# DragonBoard.net
KiCad netlist of a schematic drawn in EAGLE
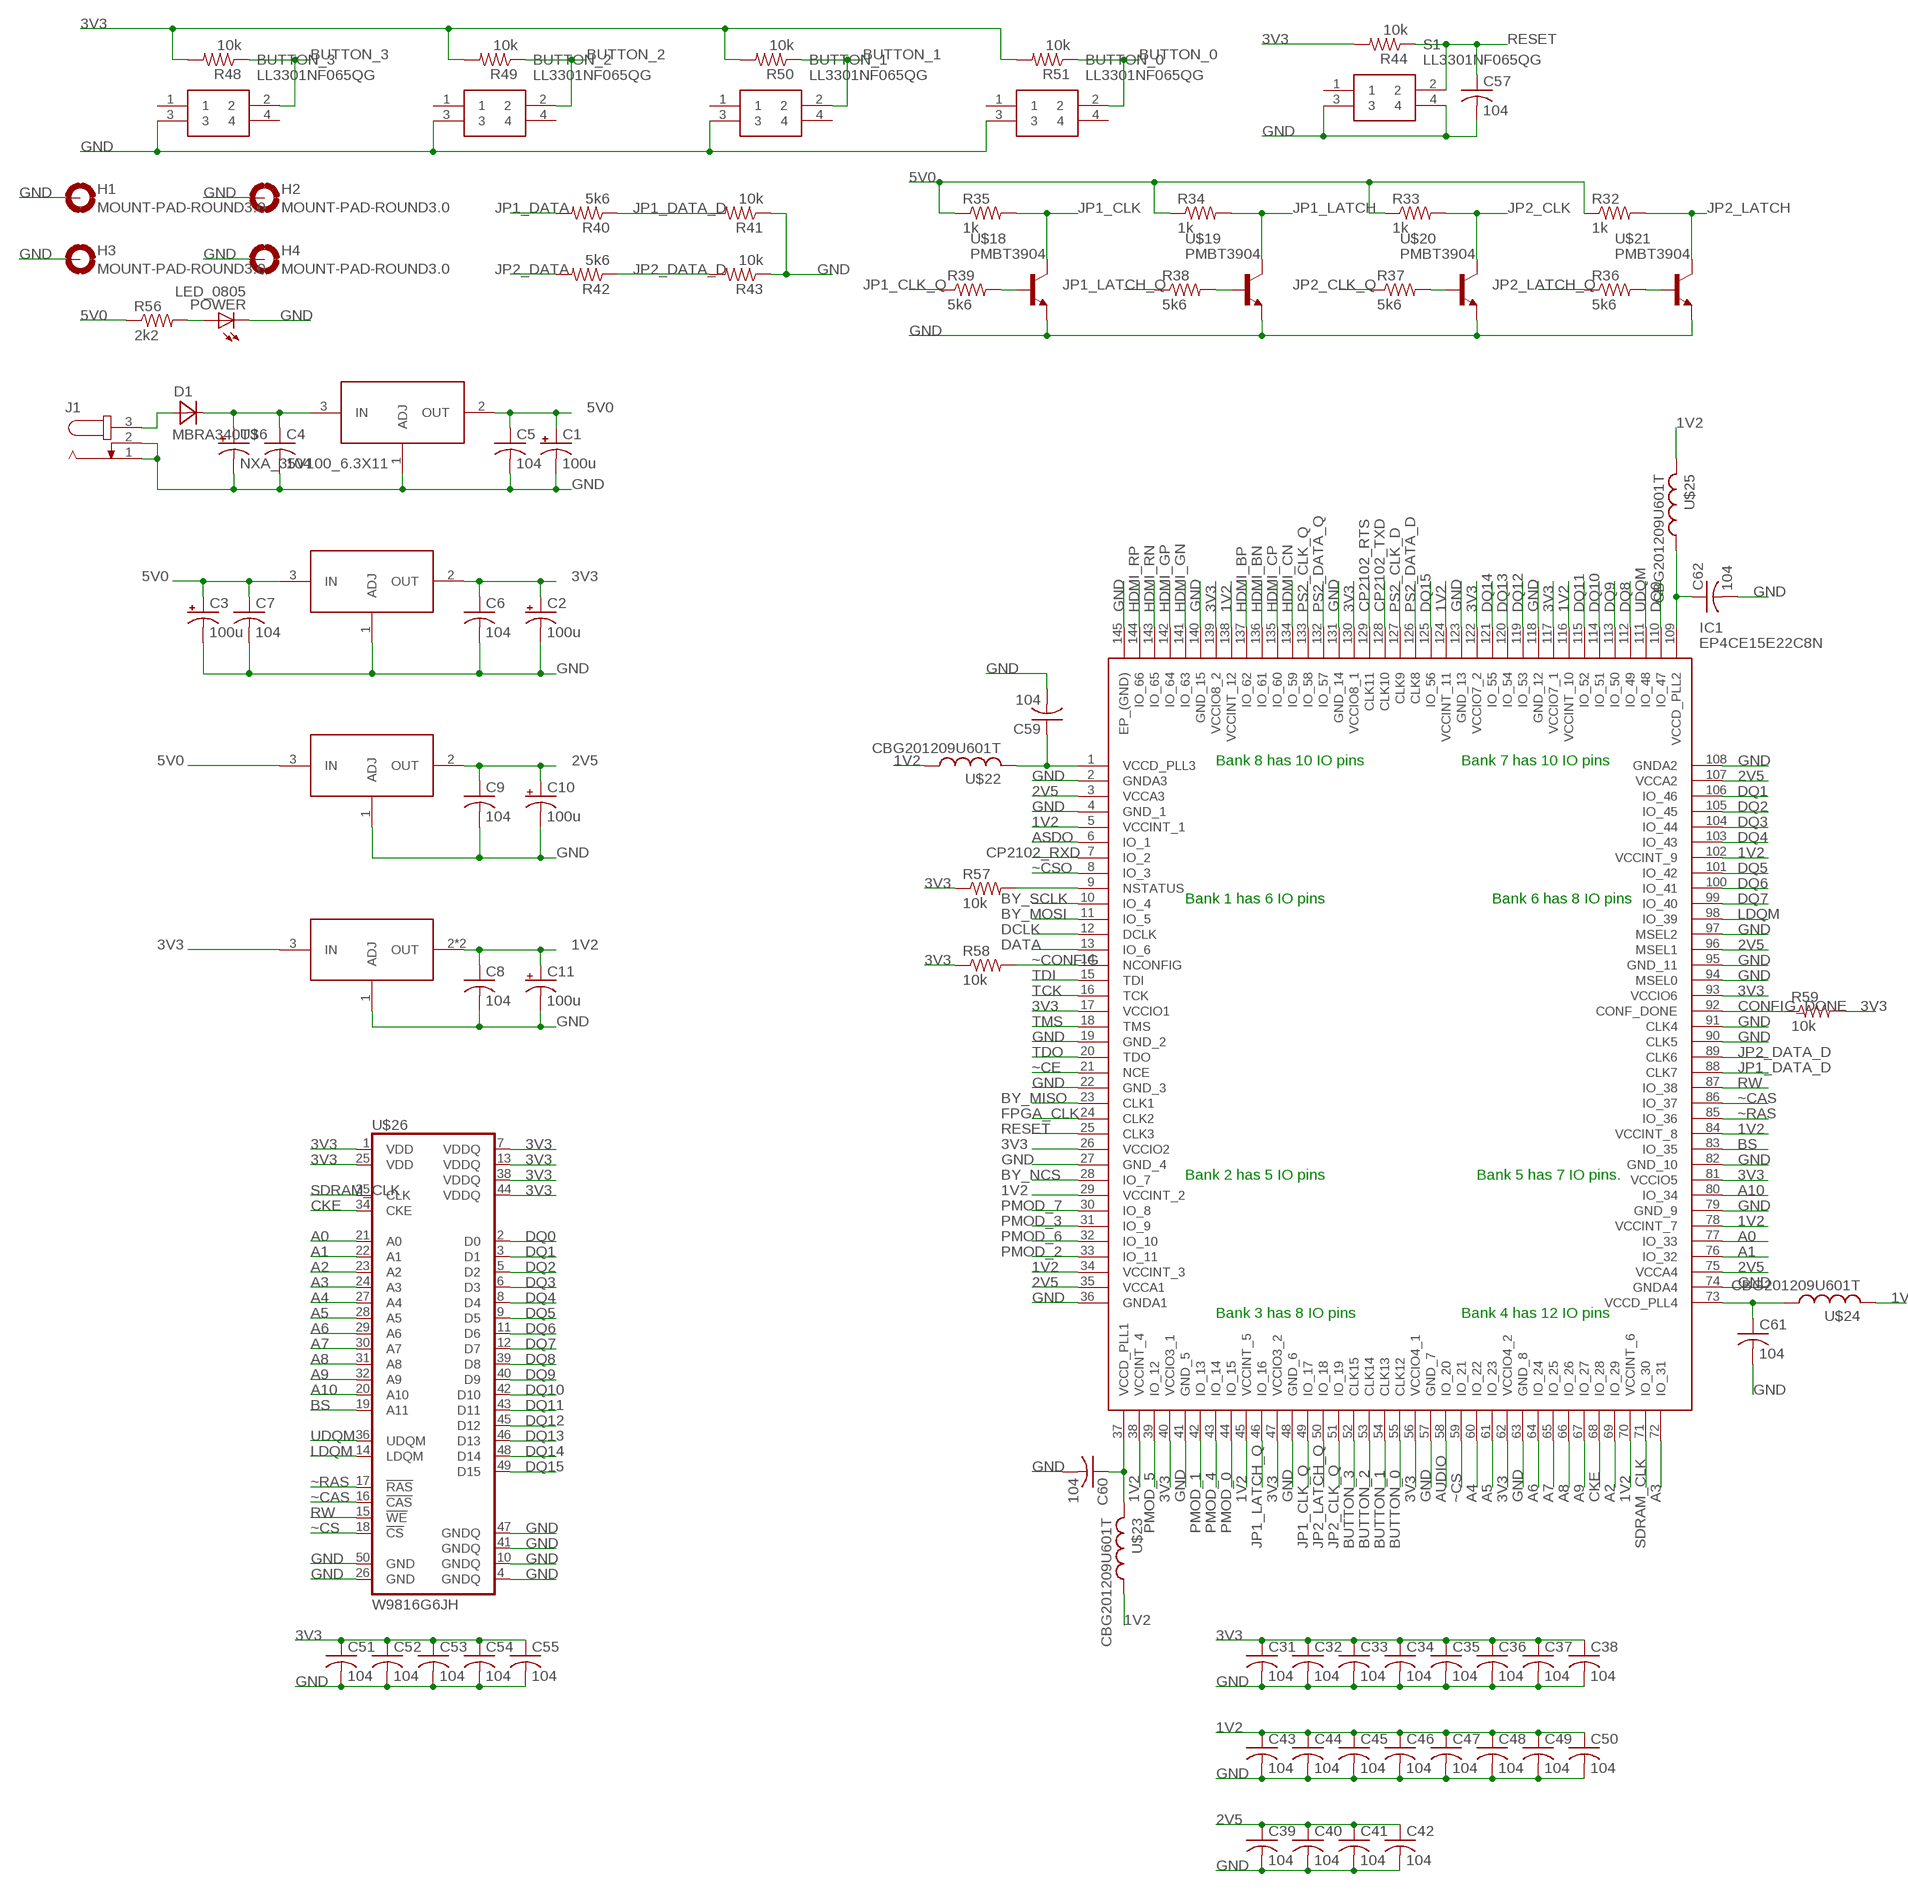
[diagram p0: schematic, sheet 1, part 1 of 2]
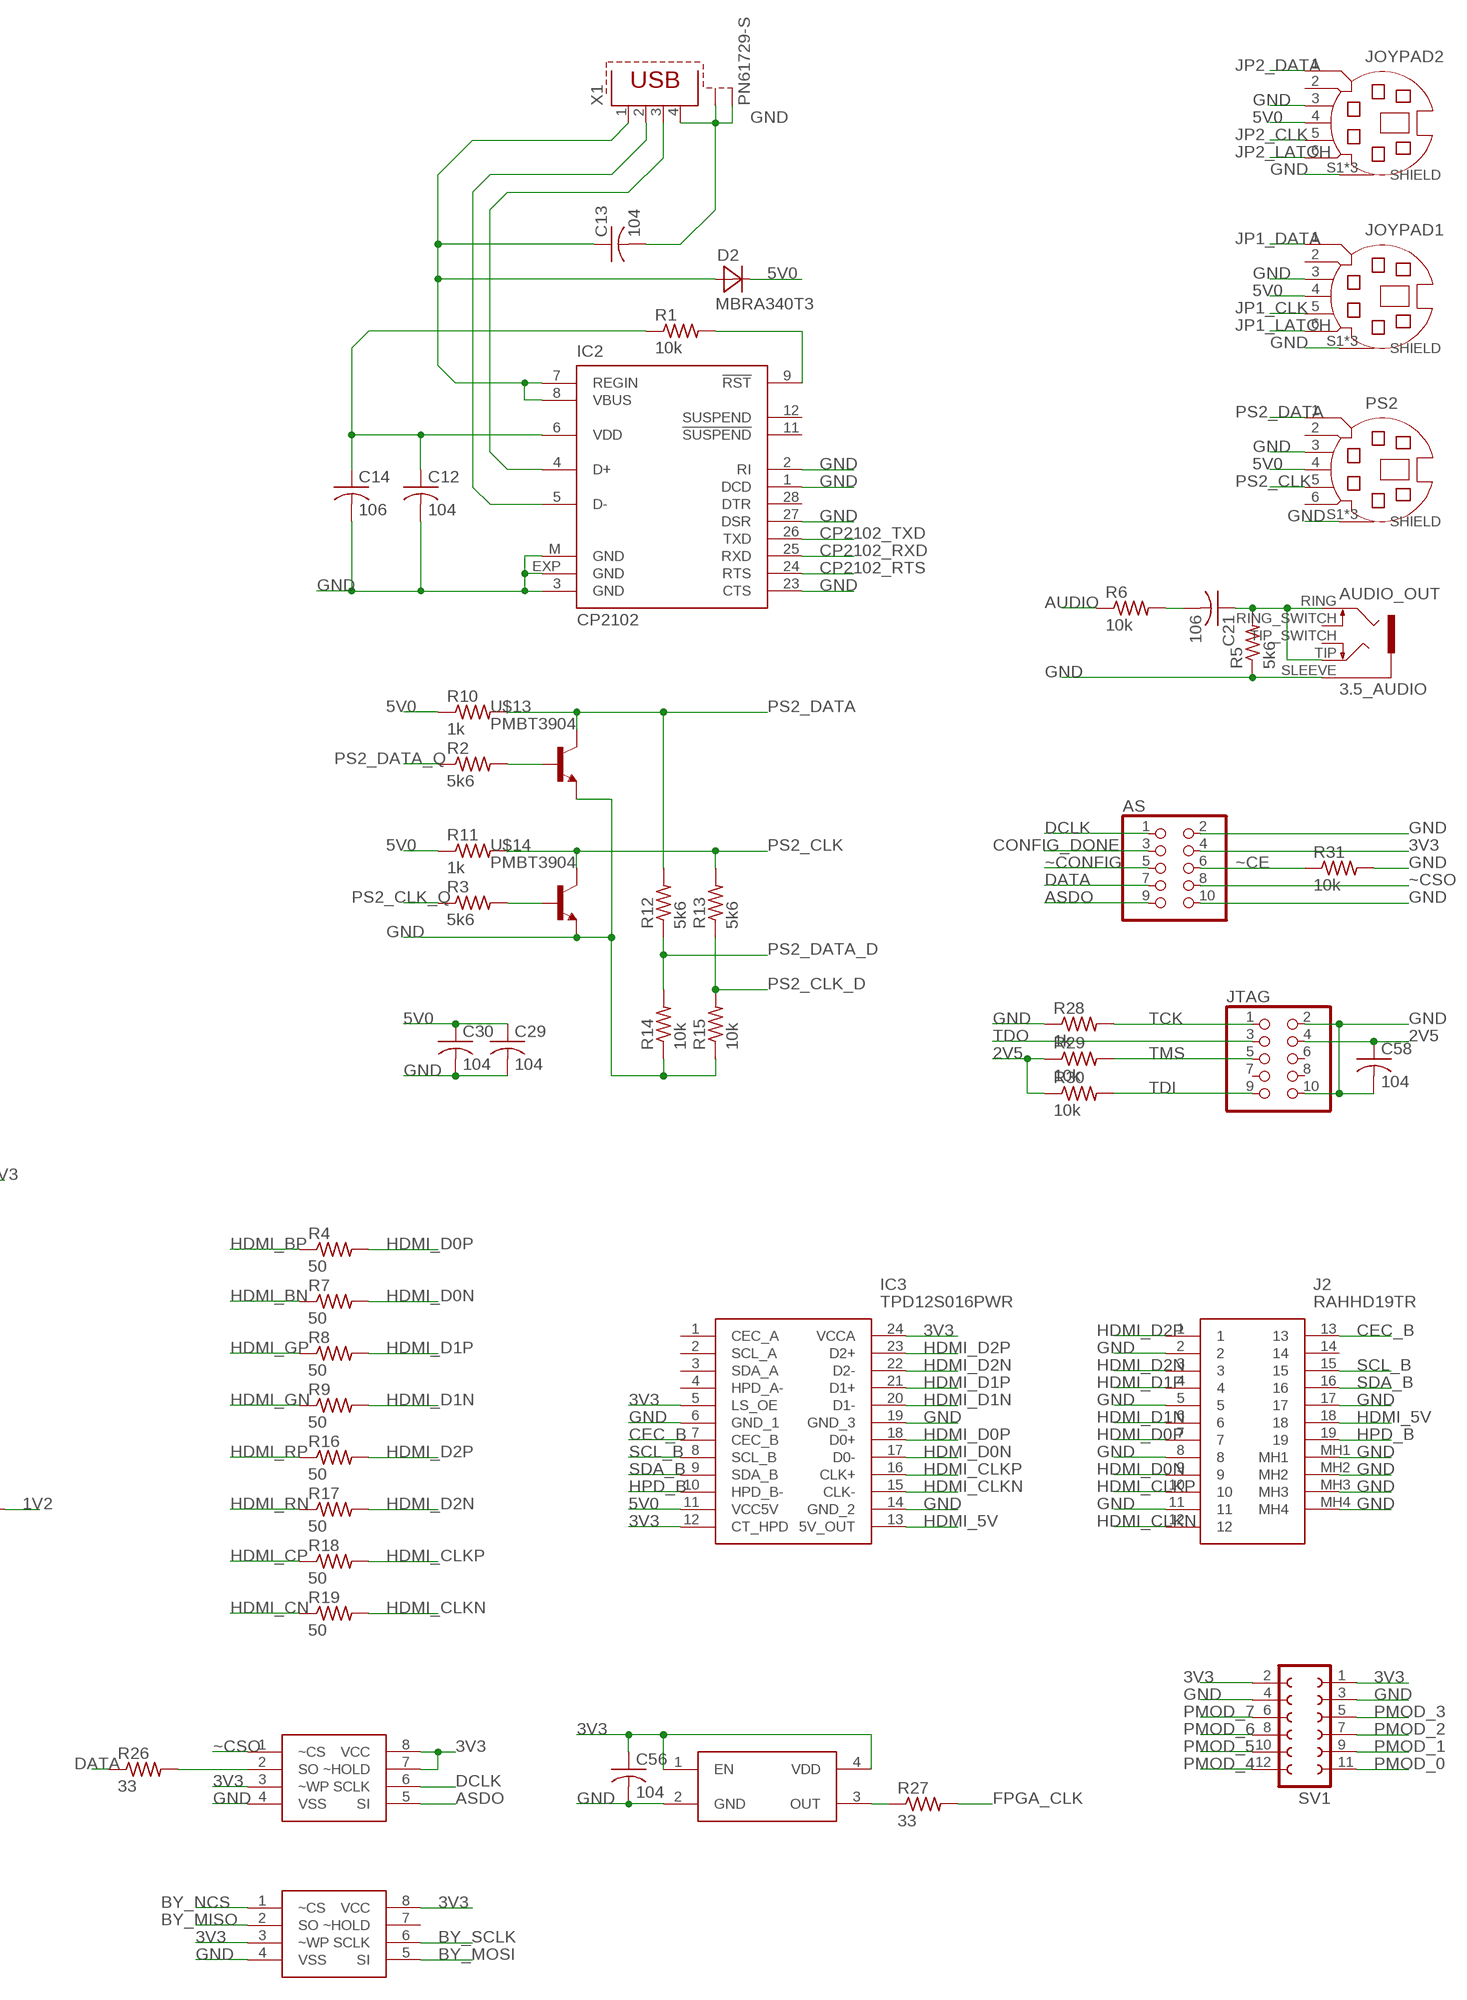
[diagram p1: schematic, sheet 1, part 2 of 2]

(export (version "E")
  (design (tool "Eeschema 10.0.6"))
  (components
    (comp (ref "AS")
      (value "PINHD-2X5")
      (footprint "eagle-import:2X05")
      (libsource (lib "eagle-import") (part "PINHD-2X5"))
    )
    (comp (ref "AUDIO_OUT")
      (value "3.5_AUDIO")
      (footprint "eagle-import:3.5_AUDIO")
      (libsource (lib "eagle-import") (part "3.5_AUDIO"))
    )
    (comp (ref "BUTTON_0")
      (value "LL3301NF065QG")
      (footprint "eagle-import:LL3301NF065QG")
      (fields (field (name "MOUSER_PART_NUMBER") "612-LL3301NF065QG"))
      (libsource (lib "eagle-import") (part "LL3301NF065QG"))
    )
    (comp (ref "BUTTON_1")
      (value "LL3301NF065QG")
      (footprint "eagle-import:LL3301NF065QG")
      (fields (field (name "MOUSER_PART_NUMBER") "612-LL3301NF065QG"))
      (libsource (lib "eagle-import") (part "LL3301NF065QG"))
    )
    (comp (ref "BUTTON_2")
      (value "LL3301NF065QG")
      (footprint "eagle-import:LL3301NF065QG")
      (fields (field (name "MOUSER_PART_NUMBER") "612-LL3301NF065QG"))
      (libsource (lib "eagle-import") (part "LL3301NF065QG"))
    )
    (comp (ref "BUTTON_3")
      (value "LL3301NF065QG")
      (footprint "eagle-import:LL3301NF065QG")
      (fields (field (name "MOUSER_PART_NUMBER") "612-LL3301NF065QG"))
      (libsource (lib "eagle-import") (part "LL3301NF065QG"))
    )
    (comp (ref "C1")
      (value "100u")
      (footprint "eagle-import:UD-6,3X5,8_NICHICON")
      (libsource (lib "eagle-import") (part "CPOL-USUD-6,3X5,8"))
    )
    (comp (ref "C2")
      (value "100u")
      (footprint "eagle-import:UD-6,3X5,8_NICHICON")
      (libsource (lib "eagle-import") (part "CPOL-USUD-6,3X5,8"))
    )
    (comp (ref "C3")
      (value "100u")
      (footprint "eagle-import:UD-6,3X5,8_NICHICON")
      (libsource (lib "eagle-import") (part "CPOL-USUD-6,3X5,8"))
    )
    (comp (ref "C4")
      (value "104")
      (footprint "eagle-import:C0805")
      (libsource (lib "eagle-import") (part "C-USC0805"))
    )
    (comp (ref "C5")
      (value "104")
      (footprint "eagle-import:C0805")
      (libsource (lib "eagle-import") (part "C-USC0805"))
    )
    (comp (ref "C6")
      (value "104")
      (footprint "eagle-import:C0805")
      (libsource (lib "eagle-import") (part "C-USC0805"))
    )
    (comp (ref "C7")
      (value "104")
      (footprint "eagle-import:C0805")
      (libsource (lib "eagle-import") (part "C-USC0805"))
    )
    (comp (ref "C8")
      (value "104")
      (footprint "eagle-import:C0805")
      (libsource (lib "eagle-import") (part "C-USC0805"))
    )
    (comp (ref "C9")
      (value "104")
      (footprint "eagle-import:C0805")
      (libsource (lib "eagle-import") (part "C-USC0805"))
    )
    (comp (ref "C10")
      (value "100u")
      (footprint "eagle-import:UD-6,3X5,8_NICHICON")
      (libsource (lib "eagle-import") (part "CPOL-USUD-6,3X5,8"))
    )
    (comp (ref "C11")
      (value "100u")
      (footprint "eagle-import:UD-6,3X5,8_NICHICON")
      (libsource (lib "eagle-import") (part "CPOL-USUD-6,3X5,8"))
    )
    (comp (ref "C12")
      (value "104")
      (footprint "eagle-import:C0805")
      (libsource (lib "eagle-import") (part "C-USC0805"))
    )
    (comp (ref "C13")
      (value "104")
      (footprint "eagle-import:C0805")
      (libsource (lib "eagle-import") (part "C-USC0805"))
    )
    (comp (ref "C14")
      (value "106")
      (footprint "eagle-import:C1206")
      (libsource (lib "eagle-import") (part "C-USC1206"))
    )
    (comp (ref "C21")
      (value "106")
      (footprint "eagle-import:C1206")
      (libsource (lib "eagle-import") (part "C-USC1206"))
    )
    (comp (ref "C29")
      (value "104")
      (footprint "eagle-import:C0805")
      (libsource (lib "eagle-import") (part "C-USC0805"))
    )
    (comp (ref "C30")
      (value "104")
      (footprint "eagle-import:C0805")
      (libsource (lib "eagle-import") (part "C-USC0805"))
    )
    (comp (ref "C31")
      (value "104")
      (footprint "eagle-import:C0805")
      (libsource (lib "eagle-import") (part "C-USC0805"))
    )
    (comp (ref "C32")
      (value "104")
      (footprint "eagle-import:C0805")
      (libsource (lib "eagle-import") (part "C-USC0805"))
    )
    (comp (ref "C33")
      (value "104")
      (footprint "eagle-import:C0805")
      (libsource (lib "eagle-import") (part "C-USC0805"))
    )
    (comp (ref "C34")
      (value "104")
      (footprint "eagle-import:C0805")
      (libsource (lib "eagle-import") (part "C-USC0805"))
    )
    (comp (ref "C35")
      (value "104")
      (footprint "eagle-import:C0805")
      (libsource (lib "eagle-import") (part "C-USC0805"))
    )
    (comp (ref "C36")
      (value "104")
      (footprint "eagle-import:C0805")
      (libsource (lib "eagle-import") (part "C-USC0805"))
    )
    (comp (ref "C37")
      (value "104")
      (footprint "eagle-import:C0805")
      (libsource (lib "eagle-import") (part "C-USC0805"))
    )
    (comp (ref "C38")
      (value "104")
      (footprint "eagle-import:C0805")
      (libsource (lib "eagle-import") (part "C-USC0805"))
    )
    (comp (ref "C39")
      (value "104")
      (footprint "eagle-import:C0805")
      (libsource (lib "eagle-import") (part "C-USC0805"))
    )
    (comp (ref "C40")
      (value "104")
      (footprint "eagle-import:C0805")
      (libsource (lib "eagle-import") (part "C-USC0805"))
    )
    (comp (ref "C41")
      (value "104")
      (footprint "eagle-import:C0805")
      (libsource (lib "eagle-import") (part "C-USC0805"))
    )
    (comp (ref "C42")
      (value "104")
      (footprint "eagle-import:C0805")
      (libsource (lib "eagle-import") (part "C-USC0805"))
    )
    (comp (ref "C43")
      (value "104")
      (footprint "eagle-import:C0805")
      (libsource (lib "eagle-import") (part "C-USC0805"))
    )
    (comp (ref "C44")
      (value "104")
      (footprint "eagle-import:C0805")
      (libsource (lib "eagle-import") (part "C-USC0805"))
    )
    (comp (ref "C45")
      (value "104")
      (footprint "eagle-import:C0805")
      (libsource (lib "eagle-import") (part "C-USC0805"))
    )
    (comp (ref "C46")
      (value "104")
      (footprint "eagle-import:C0805")
      (libsource (lib "eagle-import") (part "C-USC0805"))
    )
    (comp (ref "C47")
      (value "104")
      (footprint "eagle-import:C0805")
      (libsource (lib "eagle-import") (part "C-USC0805"))
    )
    (comp (ref "C48")
      (value "104")
      (footprint "eagle-import:C0805")
      (libsource (lib "eagle-import") (part "C-USC0805"))
    )
    (comp (ref "C49")
      (value "104")
      (footprint "eagle-import:C0805")
      (libsource (lib "eagle-import") (part "C-USC0805"))
    )
    (comp (ref "C50")
      (value "104")
      (footprint "eagle-import:C0805")
      (libsource (lib "eagle-import") (part "C-USC0805"))
    )
    (comp (ref "C51")
      (value "104")
      (footprint "eagle-import:C0805")
      (libsource (lib "eagle-import") (part "C-USC0805"))
    )
    (comp (ref "C52")
      (value "104")
      (footprint "eagle-import:C0805")
      (libsource (lib "eagle-import") (part "C-USC0805"))
    )
    (comp (ref "C53")
      (value "104")
      (footprint "eagle-import:C0805")
      (libsource (lib "eagle-import") (part "C-USC0805"))
    )
    (comp (ref "C54")
      (value "104")
      (footprint "eagle-import:C0805")
      (libsource (lib "eagle-import") (part "C-USC0805"))
    )
    (comp (ref "C55")
      (value "104")
      (footprint "eagle-import:C0805")
      (libsource (lib "eagle-import") (part "C-USC0805"))
    )
    (comp (ref "C56")
      (value "104")
      (footprint "eagle-import:C0805")
      (libsource (lib "eagle-import") (part "C-USC0805"))
    )
    (comp (ref "C57")
      (value "104")
      (footprint "eagle-import:C0805")
      (libsource (lib "eagle-import") (part "C-USC0805"))
    )
    (comp (ref "C58")
      (value "104")
      (footprint "eagle-import:C0805")
      (libsource (lib "eagle-import") (part "C-USC0805"))
    )
    (comp (ref "C59")
      (value "104")
      (footprint "eagle-import:C0805")
      (libsource (lib "eagle-import") (part "C-USC0805"))
    )
    (comp (ref "C60")
      (value "104")
      (footprint "eagle-import:C0805")
      (libsource (lib "eagle-import") (part "C-USC0805"))
    )
    (comp (ref "C61")
      (value "104")
      (footprint "eagle-import:C0805")
      (libsource (lib "eagle-import") (part "C-USC0805"))
    )
    (comp (ref "C62")
      (value "104")
      (footprint "eagle-import:C0805")
      (libsource (lib "eagle-import") (part "C-USC0805"))
    )
    (comp (ref "D1")
      (value "MBRA340T3")
      (footprint "eagle-import:SMA")
      (libsource (lib "eagle-import") (part "MBRA340T3"))
    )
    (comp (ref "D2")
      (value "MBRA340T3")
      (footprint "eagle-import:SMA")
      (libsource (lib "eagle-import") (part "MBRA340T3"))
    )
    (comp (ref "H1")
      (value "MOUNT-PAD-ROUND3.0")
      (footprint "eagle-import:3,0-PAD")
      (libsource (lib "eagle-import") (part "MOUNT-PAD-ROUND3.0"))
    )
    (comp (ref "H2")
      (value "MOUNT-PAD-ROUND3.0")
      (footprint "eagle-import:3,0-PAD")
      (libsource (lib "eagle-import") (part "MOUNT-PAD-ROUND3.0"))
    )
    (comp (ref "H3")
      (value "MOUNT-PAD-ROUND3.0")
      (footprint "eagle-import:3,0-PAD")
      (libsource (lib "eagle-import") (part "MOUNT-PAD-ROUND3.0"))
    )
    (comp (ref "H4")
      (value "MOUNT-PAD-ROUND3.0")
      (footprint "eagle-import:3,0-PAD")
      (libsource (lib "eagle-import") (part "MOUNT-PAD-ROUND3.0"))
    )
    (comp (ref "IC1")
      (value "EP4CE15E22C8N")
      (footprint "eagle-import:QFP50P2200X2200X165-145N")
      (fields (field (name "MOUSER_PART_NUMBER") "989-EP4CE15E22C8N"))
      (libsource (lib "eagle-import") (part "EP4CE15E22C8N"))
    )
    (comp (ref "IC2")
      (value "CP2102")
      (footprint "eagle-import:MLP28")
      (fields (field (name "MF") "FARNELL") (field (name "MPN") "CP2102-GM"))
      (libsource (lib "eagle-import") (part "CP2102"))
    )
    (comp (ref "IC3")
      (value "TPD12S016PWR")
      (footprint "eagle-import:SOP65P640X120-24N")
      (fields (field (name "MOUSER_PART_NUMBER") "595-TPD12S016PWR"))
      (libsource (lib "eagle-import") (part "TPD12S016PWR"))
    )
    (comp (ref "J1")
      (value "JACK-PLUG1")
      (footprint "eagle-import:SPC4078")
      (libsource (lib "eagle-import") (part "JACK-PLUG1"))
    )
    (comp (ref "J2")
      (value "RAHHD19TR")
      (footprint "eagle-import:RAHHD19TR")
      (fields (field (name "MOUSER_PART_NUMBER") "502-RAHHD19TR"))
      (libsource (lib "eagle-import") (part "RAHHD19TR"))
    )
    (comp (ref "JOYPAD1")
      (value "MD06SS")
      (footprint "eagle-import:MDIN06SS")
      (libsource (lib "eagle-import") (part "MD06SS"))
    )
    (comp (ref "JOYPAD2")
      (value "MD06SS")
      (footprint "eagle-import:MDIN06SS")
      (libsource (lib "eagle-import") (part "MD06SS"))
    )
    (comp (ref "JTAG")
      (value "PINHD-2X5")
      (footprint "eagle-import:2X05")
      (libsource (lib "eagle-import") (part "PINHD-2X5"))
    )
    (comp (ref "POWER")
      (value "LED_0805")
      (footprint "eagle-import:CHIP-LED0805")
      (libsource (lib "eagle-import") (part "LED_0805"))
    )
    (comp (ref "PS2")
      (value "MD06SS")
      (footprint "eagle-import:MDIN06SS")
      (libsource (lib "eagle-import") (part "MD06SS"))
    )
    (comp (ref "R1")
      (value "10k")
      (footprint "eagle-import:R0805")
      (libsource (lib "eagle-import") (part "R-US_R0805"))
    )
    (comp (ref "R2")
      (value "5k6")
      (footprint "eagle-import:R0805")
      (libsource (lib "eagle-import") (part "R-US_R0805"))
    )
    (comp (ref "R3")
      (value "5k6")
      (footprint "eagle-import:R0805")
      (libsource (lib "eagle-import") (part "R-US_R0805"))
    )
    (comp (ref "R4")
      (value "50")
      (footprint "eagle-import:R0805")
      (libsource (lib "eagle-import") (part "R-US_R0805"))
    )
    (comp (ref "R5")
      (value "5k6")
      (footprint "eagle-import:R0805")
      (libsource (lib "eagle-import") (part "R-US_R0805"))
    )
    (comp (ref "R6")
      (value "10k")
      (footprint "eagle-import:R0805")
      (libsource (lib "eagle-import") (part "R-US_R0805"))
    )
    (comp (ref "R7")
      (value "50")
      (footprint "eagle-import:R0805")
      (libsource (lib "eagle-import") (part "R-US_R0805"))
    )
    (comp (ref "R8")
      (value "50")
      (footprint "eagle-import:R0805")
      (libsource (lib "eagle-import") (part "R-US_R0805"))
    )
    (comp (ref "R9")
      (value "50")
      (footprint "eagle-import:R0805")
      (libsource (lib "eagle-import") (part "R-US_R0805"))
    )
    (comp (ref "R10")
      (value "1k")
      (footprint "eagle-import:R0805")
      (libsource (lib "eagle-import") (part "R-US_R0805"))
    )
    (comp (ref "R11")
      (value "1k")
      (footprint "eagle-import:R0805")
      (libsource (lib "eagle-import") (part "R-US_R0805"))
    )
    (comp (ref "R12")
      (value "5k6")
      (footprint "eagle-import:R0805")
      (libsource (lib "eagle-import") (part "R-US_R0805"))
    )
    (comp (ref "R13")
      (value "5k6")
      (footprint "eagle-import:R0805")
      (libsource (lib "eagle-import") (part "R-US_R0805"))
    )
    (comp (ref "R14")
      (value "10k")
      (footprint "eagle-import:R0805")
      (libsource (lib "eagle-import") (part "R-US_R0805"))
    )
    (comp (ref "R15")
      (value "10k")
      (footprint "eagle-import:R0805")
      (libsource (lib "eagle-import") (part "R-US_R0805"))
    )
    (comp (ref "R16")
      (value "50")
      (footprint "eagle-import:R0805")
      (libsource (lib "eagle-import") (part "R-US_R0805"))
    )
    (comp (ref "R17")
      (value "50")
      (footprint "eagle-import:R0805")
      (libsource (lib "eagle-import") (part "R-US_R0805"))
    )
    (comp (ref "R18")
      (value "50")
      (footprint "eagle-import:R0805")
      (libsource (lib "eagle-import") (part "R-US_R0805"))
    )
    (comp (ref "R19")
      (value "50")
      (footprint "eagle-import:R0805")
      (libsource (lib "eagle-import") (part "R-US_R0805"))
    )
    (comp (ref "R26")
      (value "33")
      (footprint "eagle-import:R0805")
      (libsource (lib "eagle-import") (part "R-US_R0805"))
    )
    (comp (ref "R27")
      (value "33")
      (footprint "eagle-import:R0805")
      (libsource (lib "eagle-import") (part "R-US_R0805"))
    )
    (comp (ref "R28")
      (value "1k")
      (footprint "eagle-import:R0805")
      (libsource (lib "eagle-import") (part "R-US_R0805"))
    )
    (comp (ref "R29")
      (value "10k")
      (footprint "eagle-import:R0805")
      (libsource (lib "eagle-import") (part "R-US_R0805"))
    )
    (comp (ref "R30")
      (value "10k")
      (footprint "eagle-import:R0805")
      (libsource (lib "eagle-import") (part "R-US_R0805"))
    )
    (comp (ref "R31")
      (value "10k")
      (footprint "eagle-import:R0805")
      (libsource (lib "eagle-import") (part "R-US_R0805"))
    )
    (comp (ref "R32")
      (value "1k")
      (footprint "eagle-import:R0805")
      (libsource (lib "eagle-import") (part "R-US_R0805"))
    )
    (comp (ref "R33")
      (value "1k")
      (footprint "eagle-import:R0805")
      (libsource (lib "eagle-import") (part "R-US_R0805"))
    )
    (comp (ref "R34")
      (value "1k")
      (footprint "eagle-import:R0805")
      (libsource (lib "eagle-import") (part "R-US_R0805"))
    )
    (comp (ref "R35")
      (value "1k")
      (footprint "eagle-import:R0805")
      (libsource (lib "eagle-import") (part "R-US_R0805"))
    )
    (comp (ref "R36")
      (value "5k6")
      (footprint "eagle-import:R0805")
      (libsource (lib "eagle-import") (part "R-US_R0805"))
    )
    (comp (ref "R37")
      (value "5k6")
      (footprint "eagle-import:R0805")
      (libsource (lib "eagle-import") (part "R-US_R0805"))
    )
    (comp (ref "R38")
      (value "5k6")
      (footprint "eagle-import:R0805")
      (libsource (lib "eagle-import") (part "R-US_R0805"))
    )
    (comp (ref "R39")
      (value "5k6")
      (footprint "eagle-import:R0805")
      (libsource (lib "eagle-import") (part "R-US_R0805"))
    )
    (comp (ref "R40")
      (value "5k6")
      (footprint "eagle-import:R0805")
      (libsource (lib "eagle-import") (part "R-US_R0805"))
    )
    (comp (ref "R41")
      (value "10k")
      (footprint "eagle-import:R0805")
      (libsource (lib "eagle-import") (part "R-US_R0805"))
    )
    (comp (ref "R42")
      (value "5k6")
      (footprint "eagle-import:R0805")
      (libsource (lib "eagle-import") (part "R-US_R0805"))
    )
    (comp (ref "R43")
      (value "10k")
      (footprint "eagle-import:R0805")
      (libsource (lib "eagle-import") (part "R-US_R0805"))
    )
    (comp (ref "R44")
      (value "10k")
      (footprint "eagle-import:R0805")
      (libsource (lib "eagle-import") (part "R-US_R0805"))
    )
    (comp (ref "R48")
      (value "10k")
      (footprint "eagle-import:R0805")
      (libsource (lib "eagle-import") (part "R-US_R0805"))
    )
    (comp (ref "R49")
      (value "10k")
      (footprint "eagle-import:R0805")
      (libsource (lib "eagle-import") (part "R-US_R0805"))
    )
    (comp (ref "R50")
      (value "10k")
      (footprint "eagle-import:R0805")
      (libsource (lib "eagle-import") (part "R-US_R0805"))
    )
    (comp (ref "R51")
      (value "10k")
      (footprint "eagle-import:R0805")
      (libsource (lib "eagle-import") (part "R-US_R0805"))
    )
    (comp (ref "R56")
      (value "2k2")
      (footprint "eagle-import:R0805")
      (libsource (lib "eagle-import") (part "R-US_R0805"))
    )
    (comp (ref "R57")
      (value "10k")
      (footprint "eagle-import:R0805")
      (libsource (lib "eagle-import") (part "R-US_R0805"))
    )
    (comp (ref "R58")
      (value "10k")
      (footprint "eagle-import:R0805")
      (libsource (lib "eagle-import") (part "R-US_R0805"))
    )
    (comp (ref "R59")
      (value "10k")
      (footprint "eagle-import:R0805")
      (libsource (lib "eagle-import") (part "R-US_R0805"))
    )
    (comp (ref "S1")
      (value "LL3301NF065QG")
      (footprint "eagle-import:LL3301NF065QG")
      (fields (field (name "MOUSER_PART_NUMBER") "612-LL3301NF065QG"))
      (libsource (lib "eagle-import") (part "LL3301NF065QG"))
    )
    (comp (ref "SV1")
      (value "FE06-2W")
      (footprint "eagle-import:FE06-2W")
      (libsource (lib "eagle-import") (part "FE06-2W"))
    )
    (comp (ref "U$1")
      (value "BY25Q16BS")
      (footprint "eagle-import:SO08")
      (libsource (lib "eagle-import") (part "BY25Q16BS"))
    )
    (comp (ref "U$5")
      (value "LM1086")
      (footprint "eagle-import:D2PACK")
      (libsource (lib "eagle-import") (part "LM1086"))
    )
    (comp (ref "U$6")
      (value "NXA_35V100_6.3X11")
      (footprint "eagle-import:NXA_35V100_6.3X11")
      (libsource (lib "eagle-import") (part "NXA_35V100_6.3X11"))
    )
    (comp (ref "U$7")
      (value "LD1117D-3.3")
      (footprint "eagle-import:TO252")
      (libsource (lib "eagle-import") (part "LD1117D-3.3"))
    )
    (comp (ref "U$8")
      (value "KIA1117-2.5")
      (footprint "eagle-import:SOT223")
      (libsource (lib "eagle-import") (part "KIA1117-2.5"))
    )
    (comp (ref "U$9")
      (value "AZ1117H-1.2TRG1")
      (footprint "eagle-import:SOT223")
      (libsource (lib "eagle-import") (part "AZ1117H-1.2TRG1"))
    )
    (comp (ref "U$12")
      (value "OT705050MJBA4SL")
      (footprint "eagle-import:ASV32000MHZET")
      (libsource (lib "eagle-import") (part "OT705050MJBA4SL"))
    )
    (comp (ref "U$13")
      (value "PMBT3904")
      (footprint "eagle-import:SOT23")
      (libsource (lib "eagle-import") (part "PMBT3904"))
    )
    (comp (ref "U$14")
      (value "PMBT3904")
      (footprint "eagle-import:SOT23")
      (libsource (lib "eagle-import") (part "PMBT3904"))
    )
    (comp (ref "U$16")
      (value "BY25Q16BS")
      (footprint "eagle-import:SO08")
      (libsource (lib "eagle-import") (part "BY25Q16BS"))
    )
    (comp (ref "U$18")
      (value "PMBT3904")
      (footprint "eagle-import:SOT23")
      (libsource (lib "eagle-import") (part "PMBT3904"))
    )
    (comp (ref "U$19")
      (value "PMBT3904")
      (footprint "eagle-import:SOT23")
      (libsource (lib "eagle-import") (part "PMBT3904"))
    )
    (comp (ref "U$20")
      (value "PMBT3904")
      (footprint "eagle-import:SOT23")
      (libsource (lib "eagle-import") (part "PMBT3904"))
    )
    (comp (ref "U$21")
      (value "PMBT3904")
      (footprint "eagle-import:SOT23")
      (libsource (lib "eagle-import") (part "PMBT3904"))
    )
    (comp (ref "U$22")
      (value "CBG201209U601T")
      (footprint "eagle-import:C0805")
      (libsource (lib "eagle-import") (part "CBG201209U601T"))
    )
    (comp (ref "U$23")
      (value "CBG201209U601T")
      (footprint "eagle-import:C0805")
      (libsource (lib "eagle-import") (part "CBG201209U601T"))
    )
    (comp (ref "U$24")
      (value "CBG201209U601T")
      (footprint "eagle-import:C0805")
      (libsource (lib "eagle-import") (part "CBG201209U601T"))
    )
    (comp (ref "U$25")
      (value "CBG201209U601T")
      (footprint "eagle-import:C0805")
      (libsource (lib "eagle-import") (part "CBG201209U601T"))
    )
    (comp (ref "U$26")
      (value "W9816G6JH")
      (footprint "eagle-import:TSOP50-II")
      (libsource (lib "eagle-import") (part "W9816G6JH"))
    )
    (comp (ref "X1")
      (value "PN61729-S")
      (footprint "eagle-import:PN61729-S")
      (libsource (lib "eagle-import") (part "PN61729-S"))
    )
  )
  (nets
    (net (code "1") (name "/1V2") (class "Default")
      (node (ref "C11") (pin "+") (pinfunction "+_+") (pintype "passive"))
      (node (ref "C43") (pin "1") (pinfunction "1_1") (pintype "passive"))
      (node (ref "C44") (pin "1") (pinfunction "1_1") (pintype "passive"))
      (node (ref "C45") (pin "1") (pinfunction "1_1") (pintype "passive"))
      (node (ref "C46") (pin "1") (pinfunction "1_1") (pintype "passive"))
      (node (ref "C47") (pin "1") (pinfunction "1_1") (pintype "passive"))
      (node (ref "C48") (pin "1") (pinfunction "1_1") (pintype "passive"))
      (node (ref "C49") (pin "1") (pinfunction "1_1") (pintype "passive"))
      (node (ref "C50") (pin "1") (pinfunction "1_1") (pintype "passive"))
      (node (ref "C8") (pin "1") (pinfunction "1_1") (pintype "passive"))
      (node (ref "IC1") (pin "102") (pinfunction "VCCINT_9_102") (pintype "bidirectional"))
      (node (ref "IC1") (pin "116") (pinfunction "VCCINT_10_116") (pintype "bidirectional"))
      (node (ref "IC1") (pin "124") (pinfunction "VCCINT_11_124") (pintype "bidirectional"))
      (node (ref "IC1") (pin "138") (pinfunction "VCCINT_12_138") (pintype "bidirectional"))
      (node (ref "IC1") (pin "29") (pinfunction "VCCINT_2_29") (pintype "bidirectional"))
      (node (ref "IC1") (pin "34") (pinfunction "VCCINT_3_34") (pintype "bidirectional"))
      (node (ref "IC1") (pin "38") (pinfunction "VCCINT_4_38") (pintype "bidirectional"))
      (node (ref "IC1") (pin "45") (pinfunction "VCCINT_5_45") (pintype "bidirectional"))
      (node (ref "IC1") (pin "5") (pinfunction "VCCINT_1_5") (pintype "bidirectional"))
      (node (ref "IC1") (pin "70") (pinfunction "VCCINT_6_70") (pintype "bidirectional"))
      (node (ref "IC1") (pin "78") (pinfunction "VCCINT_7_78") (pintype "bidirectional"))
      (node (ref "IC1") (pin "84") (pinfunction "VCCINT_8_84") (pintype "bidirectional"))
      (node (ref "U$22") (pin "1") (pinfunction "1_1") (pintype "passive"))
      (node (ref "U$23") (pin "1") (pinfunction "1_1") (pintype "passive"))
      (node (ref "U$24") (pin "2") (pinfunction "2_2") (pintype "passive"))
      (node (ref "U$25") (pin "2") (pinfunction "2_2") (pintype "passive"))
      (node (ref "U$9") (pin "2") (pinfunction "OUT_2") (pintype "bidirectional"))
      (node (ref "U$9") (pin "4") (pinfunction "OUT_4") (pintype "bidirectional"))
    )
    (net (code "2") (name "/2V5") (class "Default")
      (node (ref "C10") (pin "+") (pinfunction "+_+") (pintype "passive"))
      (node (ref "C39") (pin "1") (pinfunction "1_1") (pintype "passive"))
      (node (ref "C40") (pin "1") (pinfunction "1_1") (pintype "passive"))
      (node (ref "C41") (pin "1") (pinfunction "1_1") (pintype "passive"))
      (node (ref "C42") (pin "1") (pinfunction "1_1") (pintype "passive"))
      (node (ref "C58") (pin "1") (pinfunction "1_1") (pintype "passive"))
      (node (ref "C9") (pin "1") (pinfunction "1_1") (pintype "passive"))
      (node (ref "IC1") (pin "107") (pinfunction "VCCA2_107") (pintype "bidirectional"))
      (node (ref "IC1") (pin "3") (pinfunction "VCCA3_3") (pintype "bidirectional"))
      (node (ref "IC1") (pin "35") (pinfunction "VCCA1_35") (pintype "bidirectional"))
      (node (ref "IC1") (pin "75") (pinfunction "VCCA4_75") (pintype "bidirectional"))
      (node (ref "IC1") (pin "96") (pinfunction "MSEL1_96") (pintype "bidirectional"))
      (node (ref "JTAG") (pin "4") (pinfunction "4_4") (pintype "passive"))
      (node (ref "R29") (pin "1") (pinfunction "1_1") (pintype "passive"))
      (node (ref "R30") (pin "1") (pinfunction "1_1") (pintype "passive"))
      (node (ref "U$8") (pin "2") (pinfunction "OUT_2") (pintype "bidirectional"))
    )
    (net (code "3") (name "/3V3") (class "Default")
      (node (ref "AS") (pin "4") (pinfunction "4_4") (pintype "passive"))
      (node (ref "C2") (pin "+") (pinfunction "+_+") (pintype "passive"))
      (node (ref "C31") (pin "1") (pinfunction "1_1") (pintype "passive"))
      (node (ref "C32") (pin "1") (pinfunction "1_1") (pintype "passive"))
      (node (ref "C33") (pin "1") (pinfunction "1_1") (pintype "passive"))
      (node (ref "C34") (pin "1") (pinfunction "1_1") (pintype "passive"))
      (node (ref "C35") (pin "1") (pinfunction "1_1") (pintype "passive"))
      (node (ref "C36") (pin "1") (pinfunction "1_1") (pintype "passive"))
      (node (ref "C37") (pin "1") (pinfunction "1_1") (pintype "passive"))
      (node (ref "C38") (pin "1") (pinfunction "1_1") (pintype "passive"))
      (node (ref "C51") (pin "1") (pinfunction "1_1") (pintype "passive"))
      (node (ref "C52") (pin "1") (pinfunction "1_1") (pintype "passive"))
      (node (ref "C53") (pin "1") (pinfunction "1_1") (pintype "passive"))
      (node (ref "C54") (pin "1") (pinfunction "1_1") (pintype "passive"))
      (node (ref "C55") (pin "1") (pinfunction "1_1") (pintype "passive"))
      (node (ref "C56") (pin "1") (pinfunction "1_1") (pintype "passive"))
      (node (ref "C6") (pin "1") (pinfunction "1_1") (pintype "passive"))
      (node (ref "IC1") (pin "117") (pinfunction "VCCIO7_1_117") (pintype "bidirectional"))
      (node (ref "IC1") (pin "122") (pinfunction "VCCIO7_2_122") (pintype "bidirectional"))
      (node (ref "IC1") (pin "130") (pinfunction "VCCIO8_1_130") (pintype "bidirectional"))
      (node (ref "IC1") (pin "139") (pinfunction "VCCIO8_2_139") (pintype "bidirectional"))
      (node (ref "IC1") (pin "17") (pinfunction "VCCIO1_17") (pintype "bidirectional"))
      (node (ref "IC1") (pin "26") (pinfunction "VCCIO2_26") (pintype "bidirectional"))
      (node (ref "IC1") (pin "40") (pinfunction "VCCIO3_1_40") (pintype "bidirectional"))
      (node (ref "IC1") (pin "47") (pinfunction "VCCIO3_2_47") (pintype "bidirectional"))
      (node (ref "IC1") (pin "56") (pinfunction "VCCIO4_1_56") (pintype "bidirectional"))
      (node (ref "IC1") (pin "62") (pinfunction "VCCIO4_2_62") (pintype "bidirectional"))
      (node (ref "IC1") (pin "81") (pinfunction "VCCIO5_81") (pintype "bidirectional"))
      (node (ref "IC1") (pin "93") (pinfunction "VCCIO6_93") (pintype "bidirectional"))
      (node (ref "IC3") (pin "12") (pinfunction "CT_HPD_12") (pintype "bidirectional"))
      (node (ref "IC3") (pin "24") (pinfunction "VCCA_24") (pintype "power_in"))
      (node (ref "IC3") (pin "5") (pinfunction "LS_OE_5") (pintype "bidirectional"))
      (node (ref "R44") (pin "2") (pinfunction "2_2") (pintype "passive"))
      (node (ref "R48") (pin "2") (pinfunction "2_2") (pintype "passive"))
      (node (ref "R49") (pin "2") (pinfunction "2_2") (pintype "passive"))
      (node (ref "R50") (pin "2") (pinfunction "2_2") (pintype "passive"))
      (node (ref "R51") (pin "2") (pinfunction "2_2") (pintype "passive"))
      (node (ref "R57") (pin "1") (pinfunction "1_1") (pintype "passive"))
      (node (ref "R58") (pin "1") (pinfunction "1_1") (pintype "passive"))
      (node (ref "R59") (pin "2") (pinfunction "2_2") (pintype "passive"))
      (node (ref "SV1") (pin "1") (pinfunction "1_1") (pintype "passive"))
      (node (ref "SV1") (pin "2") (pinfunction "2_2") (pintype "passive"))
      (node (ref "U$1") (pin "3") (pinfunction "~{WP}_3") (pintype "bidirectional"))
      (node (ref "U$1") (pin "8") (pinfunction "VCC_8") (pintype "bidirectional"))
      (node (ref "U$12") (pin "1") (pinfunction "EN_1") (pintype "bidirectional"))
      (node (ref "U$12") (pin "4") (pinfunction "VDD_4") (pintype "bidirectional"))
      (node (ref "U$16") (pin "3") (pinfunction "~{WP}_3") (pintype "bidirectional"))
      (node (ref "U$16") (pin "7") (pinfunction "~{HOLD}_7") (pintype "bidirectional"))
      (node (ref "U$16") (pin "8") (pinfunction "VCC_8") (pintype "bidirectional"))
      (node (ref "U$26") (pin "1") (pinfunction "VDD_1") (pintype "power_in"))
      (node (ref "U$26") (pin "13") (pinfunction "VDDQ_13") (pintype "power_in"))
      (node (ref "U$26") (pin "25") (pinfunction "VDD_25") (pintype "power_in"))
      (node (ref "U$26") (pin "38") (pinfunction "VDDQ_38") (pintype "power_in"))
      (node (ref "U$26") (pin "44") (pinfunction "VDDQ_44") (pintype "power_in"))
      (node (ref "U$26") (pin "7") (pinfunction "VDDQ_7") (pintype "power_in"))
      (node (ref "U$7") (pin "2") (pinfunction "OUT_2") (pintype "bidirectional"))
      (node (ref "U$9") (pin "3") (pinfunction "IN_3") (pintype "bidirectional"))
    )
    (net (code "4") (name "/5V0") (class "Default")
      (node (ref "C1") (pin "+") (pinfunction "+_+") (pintype "passive"))
      (node (ref "C29") (pin "1") (pinfunction "1_1") (pintype "passive"))
      (node (ref "C3") (pin "+") (pinfunction "+_+") (pintype "passive"))
      (node (ref "C30") (pin "1") (pinfunction "1_1") (pintype "passive"))
      (node (ref "C5") (pin "1") (pinfunction "1_1") (pintype "passive"))
      (node (ref "C7") (pin "1") (pinfunction "1_1") (pintype "passive"))
      (node (ref "D2") (pin "C") (pinfunction "C_C") (pintype "passive"))
      (node (ref "IC3") (pin "11") (pinfunction "VCC5V_11") (pintype "power_in"))
      (node (ref "JOYPAD1") (pin "4") (pinfunction "4_4") (pintype "passive"))
      (node (ref "JOYPAD2") (pin "4") (pinfunction "4_4") (pintype "passive"))
      (node (ref "PS2") (pin "4") (pinfunction "4_4") (pintype "passive"))
      (node (ref "R10") (pin "1") (pinfunction "1_1") (pintype "passive"))
      (node (ref "R11") (pin "1") (pinfunction "1_1") (pintype "passive"))
      (node (ref "R32") (pin "1") (pinfunction "1_1") (pintype "passive"))
      (node (ref "R33") (pin "1") (pinfunction "1_1") (pintype "passive"))
      (node (ref "R34") (pin "1") (pinfunction "1_1") (pintype "passive"))
      (node (ref "R35") (pin "1") (pinfunction "1_1") (pintype "passive"))
      (node (ref "R56") (pin "1") (pinfunction "1_1") (pintype "passive"))
      (node (ref "U$5") (pin "2") (pinfunction "OUT_2") (pintype "bidirectional"))
      (node (ref "U$7") (pin "3") (pinfunction "IN_3") (pintype "bidirectional"))
      (node (ref "U$8") (pin "3") (pinfunction "IN_3") (pintype "bidirectional"))
    )
    (net (code "5") (name "/A0") (class "Default")
      (node (ref "IC1") (pin "77") (pinfunction "IO_33_77") (pintype "bidirectional"))
      (node (ref "U$26") (pin "21") (pinfunction "A0_21") (pintype "input"))
    )
    (net (code "6") (name "/A1") (class "Default")
      (node (ref "IC1") (pin "76") (pinfunction "IO_32_76") (pintype "bidirectional"))
      (node (ref "U$26") (pin "22") (pinfunction "A1_22") (pintype "input"))
    )
    (net (code "7") (name "/A2") (class "Default")
      (node (ref "IC1") (pin "69") (pinfunction "IO_29_69") (pintype "bidirectional"))
      (node (ref "U$26") (pin "23") (pinfunction "A2_23") (pintype "input"))
    )
    (net (code "8") (name "/A3") (class "Default")
      (node (ref "IC1") (pin "72") (pinfunction "IO_31_72") (pintype "bidirectional"))
      (node (ref "U$26") (pin "24") (pinfunction "A3_24") (pintype "input"))
    )
    (net (code "9") (name "/A4") (class "Default")
      (node (ref "IC1") (pin "60") (pinfunction "IO_22_60") (pintype "bidirectional"))
      (node (ref "U$26") (pin "27") (pinfunction "A4_27") (pintype "input"))
    )
    (net (code "10") (name "/A5") (class "Default")
      (node (ref "IC1") (pin "61") (pinfunction "IO_23_61") (pintype "bidirectional"))
      (node (ref "U$26") (pin "28") (pinfunction "A5_28") (pintype "input"))
    )
    (net (code "11") (name "/A6") (class "Default")
      (node (ref "IC1") (pin "64") (pinfunction "IO_24_64") (pintype "bidirectional"))
      (node (ref "U$26") (pin "29") (pinfunction "A6_29") (pintype "input"))
    )
    (net (code "12") (name "/A7") (class "Default")
      (node (ref "IC1") (pin "65") (pinfunction "IO_25_65") (pintype "bidirectional"))
      (node (ref "U$26") (pin "30") (pinfunction "A7_30") (pintype "input"))
    )
    (net (code "13") (name "/A8") (class "Default")
      (node (ref "IC1") (pin "66") (pinfunction "IO_26_66") (pintype "bidirectional"))
      (node (ref "U$26") (pin "31") (pinfunction "A8_31") (pintype "input"))
    )
    (net (code "14") (name "/A9") (class "Default")
      (node (ref "IC1") (pin "67") (pinfunction "IO_27_67") (pintype "bidirectional"))
      (node (ref "U$26") (pin "32") (pinfunction "A9_32") (pintype "input"))
    )
    (net (code "15") (name "/A10") (class "Default")
      (node (ref "IC1") (pin "80") (pinfunction "IO_34_80") (pintype "bidirectional"))
      (node (ref "U$26") (pin "20") (pinfunction "A10_20") (pintype "input"))
    )
    (net (code "16") (name "/ASDO") (class "Default")
      (node (ref "AS") (pin "9") (pinfunction "9_9") (pintype "passive"))
      (node (ref "IC1") (pin "6") (pinfunction "IO_1_6") (pintype "bidirectional"))
      (node (ref "U$16") (pin "5") (pinfunction "SI_5") (pintype "bidirectional"))
    )
    (net (code "17") (name "/AUDIO") (class "Default")
      (node (ref "IC1") (pin "58") (pinfunction "IO_20_58") (pintype "bidirectional"))
      (node (ref "R6") (pin "1") (pinfunction "1_1") (pintype "passive"))
    )
    (net (code "18") (name "/BS") (class "Default")
      (node (ref "IC1") (pin "83") (pinfunction "IO_35_83") (pintype "bidirectional"))
      (node (ref "U$26") (pin "19") (pinfunction "A11_19") (pintype "input"))
    )
    (net (code "19") (name "/BUTTON_0") (class "Default")
      (node (ref "BUTTON_0") (pin "2") (pinfunction "2_2") (pintype "bidirectional"))
      (node (ref "IC1") (pin "55") (pinfunction "CLK12_55") (pintype "bidirectional"))
      (node (ref "R51") (pin "1") (pinfunction "1_1") (pintype "passive"))
    )
    (net (code "20") (name "/BUTTON_1") (class "Default")
      (node (ref "BUTTON_1") (pin "2") (pinfunction "2_2") (pintype "bidirectional"))
      (node (ref "IC1") (pin "54") (pinfunction "CLK13_54") (pintype "bidirectional"))
      (node (ref "R50") (pin "1") (pinfunction "1_1") (pintype "passive"))
    )
    (net (code "21") (name "/BUTTON_2") (class "Default")
      (node (ref "BUTTON_2") (pin "2") (pinfunction "2_2") (pintype "bidirectional"))
      (node (ref "IC1") (pin "53") (pinfunction "CLK14_53") (pintype "bidirectional"))
      (node (ref "R49") (pin "1") (pinfunction "1_1") (pintype "passive"))
    )
    (net (code "22") (name "/BUTTON_3") (class "Default")
      (node (ref "BUTTON_3") (pin "2") (pinfunction "2_2") (pintype "bidirectional"))
      (node (ref "IC1") (pin "52") (pinfunction "CLK15_52") (pintype "bidirectional"))
      (node (ref "R48") (pin "1") (pinfunction "1_1") (pintype "passive"))
    )
    (net (code "23") (name "/BY_MISO") (class "Default")
      (node (ref "IC1") (pin "23") (pinfunction "CLK1_23") (pintype "bidirectional"))
      (node (ref "U$1") (pin "2") (pinfunction "SO_2") (pintype "bidirectional"))
    )
    (net (code "24") (name "/BY_MOSI") (class "Default")
      (node (ref "IC1") (pin "11") (pinfunction "IO_5_11") (pintype "bidirectional"))
      (node (ref "U$1") (pin "5") (pinfunction "SI_5") (pintype "bidirectional"))
    )
    (net (code "25") (name "/BY_NCS") (class "Default")
      (node (ref "IC1") (pin "28") (pinfunction "IO_7_28") (pintype "bidirectional"))
      (node (ref "U$1") (pin "1") (pinfunction "~{CS}_1") (pintype "bidirectional"))
    )
    (net (code "26") (name "/BY_SCLK") (class "Default")
      (node (ref "IC1") (pin "10") (pinfunction "IO_4_10") (pintype "bidirectional"))
      (node (ref "U$1") (pin "6") (pinfunction "SCLK_6") (pintype "bidirectional"))
    )
    (net (code "27") (name "/CEC_B") (class "Default")
      (node (ref "IC3") (pin "7") (pinfunction "CEC_B_7") (pintype "bidirectional"))
      (node (ref "J2") (pin "13") (pinfunction "13_13") (pintype "bidirectional"))
    )
    (net (code "28") (name "/CKE") (class "Default")
      (node (ref "IC1") (pin "68") (pinfunction "IO_28_68") (pintype "bidirectional"))
      (node (ref "U$26") (pin "34") (pinfunction "CKE_34") (pintype "input"))
    )
    (net (code "29") (name "/CONFIG_DONE") (class "Default")
      (node (ref "AS") (pin "3") (pinfunction "3_3") (pintype "passive"))
      (node (ref "IC1") (pin "92") (pinfunction "CONF_DONE_92") (pintype "bidirectional"))
      (node (ref "R59") (pin "1") (pinfunction "1_1") (pintype "passive"))
    )
    (net (code "30") (name "/CP2102_RTS") (class "Default")
      (node (ref "IC1") (pin "129") (pinfunction "CLK11_129") (pintype "bidirectional"))
      (node (ref "IC2") (pin "24") (pinfunction "RTS_24") (pintype "output"))
    )
    (net (code "31") (name "/CP2102_RXD") (class "Default")
      (node (ref "IC1") (pin "7") (pinfunction "IO_2_7") (pintype "bidirectional"))
      (node (ref "IC2") (pin "25") (pinfunction "RXD_25") (pintype "input"))
    )
    (net (code "32") (name "/CP2102_TXD") (class "Default")
      (node (ref "IC1") (pin "128") (pinfunction "CLK10_128") (pintype "bidirectional"))
      (node (ref "IC2") (pin "26") (pinfunction "TXD_26") (pintype "output"))
    )
    (net (code "33") (name "/DATA") (class "Default")
      (node (ref "AS") (pin "7") (pinfunction "7_7") (pintype "passive"))
      (node (ref "IC1") (pin "13") (pinfunction "IO_6_13") (pintype "bidirectional"))
      (node (ref "R26") (pin "1") (pinfunction "1_1") (pintype "passive"))
    )
    (net (code "34") (name "/DCLK") (class "Default")
      (node (ref "AS") (pin "1") (pinfunction "1_1") (pintype "passive"))
      (node (ref "IC1") (pin "12") (pinfunction "DCLK_12") (pintype "bidirectional"))
      (node (ref "U$16") (pin "6") (pinfunction "SCLK_6") (pintype "bidirectional"))
    )
    (net (code "35") (name "/DQ0") (class "Default")
      (node (ref "IC1") (pin "110") (pinfunction "IO_47_110") (pintype "bidirectional"))
      (node (ref "U$26") (pin "2") (pinfunction "D0_2") (pintype "bidirectional"))
    )
    (net (code "36") (name "/DQ1") (class "Default")
      (node (ref "IC1") (pin "106") (pinfunction "IO_46_106") (pintype "bidirectional"))
      (node (ref "U$26") (pin "3") (pinfunction "D1_3") (pintype "bidirectional"))
    )
    (net (code "37") (name "/DQ2") (class "Default")
      (node (ref "IC1") (pin "105") (pinfunction "IO_45_105") (pintype "bidirectional"))
      (node (ref "U$26") (pin "5") (pinfunction "D2_5") (pintype "bidirectional"))
    )
    (net (code "38") (name "/DQ3") (class "Default")
      (node (ref "IC1") (pin "104") (pinfunction "IO_44_104") (pintype "bidirectional"))
      (node (ref "U$26") (pin "6") (pinfunction "D3_6") (pintype "bidirectional"))
    )
    (net (code "39") (name "/DQ4") (class "Default")
      (node (ref "IC1") (pin "103") (pinfunction "IO_43_103") (pintype "bidirectional"))
      (node (ref "U$26") (pin "8") (pinfunction "D4_8") (pintype "bidirectional"))
    )
    (net (code "40") (name "/DQ5") (class "Default")
      (node (ref "IC1") (pin "101") (pinfunction "IO_42_101") (pintype "bidirectional"))
      (node (ref "U$26") (pin "9") (pinfunction "D5_9") (pintype "bidirectional"))
    )
    (net (code "41") (name "/DQ6") (class "Default")
      (node (ref "IC1") (pin "100") (pinfunction "IO_41_100") (pintype "bidirectional"))
      (node (ref "U$26") (pin "11") (pinfunction "D6_11") (pintype "bidirectional"))
    )
    (net (code "42") (name "/DQ7") (class "Default")
      (node (ref "IC1") (pin "99") (pinfunction "IO_40_99") (pintype "bidirectional"))
      (node (ref "U$26") (pin "12") (pinfunction "D7_12") (pintype "bidirectional"))
    )
    (net (code "43") (name "/DQ8") (class "Default")
      (node (ref "IC1") (pin "112") (pinfunction "IO_49_112") (pintype "bidirectional"))
      (node (ref "U$26") (pin "39") (pinfunction "D8_39") (pintype "bidirectional"))
    )
    (net (code "44") (name "/DQ9") (class "Default")
      (node (ref "IC1") (pin "113") (pinfunction "IO_50_113") (pintype "bidirectional"))
      (node (ref "U$26") (pin "40") (pinfunction "D9_40") (pintype "bidirectional"))
    )
    (net (code "45") (name "/DQ10") (class "Default")
      (node (ref "IC1") (pin "114") (pinfunction "IO_51_114") (pintype "bidirectional"))
      (node (ref "U$26") (pin "42") (pinfunction "D10_42") (pintype "bidirectional"))
    )
    (net (code "46") (name "/DQ11") (class "Default")
      (node (ref "IC1") (pin "115") (pinfunction "IO_52_115") (pintype "bidirectional"))
      (node (ref "U$26") (pin "43") (pinfunction "D11_43") (pintype "bidirectional"))
    )
    (net (code "47") (name "/DQ12") (class "Default")
      (node (ref "IC1") (pin "119") (pinfunction "IO_53_119") (pintype "bidirectional"))
      (node (ref "U$26") (pin "45") (pinfunction "D12_45") (pintype "bidirectional"))
    )
    (net (code "48") (name "/DQ13") (class "Default")
      (node (ref "IC1") (pin "120") (pinfunction "IO_54_120") (pintype "bidirectional"))
      (node (ref "U$26") (pin "46") (pinfunction "D13_46") (pintype "bidirectional"))
    )
    (net (code "49") (name "/DQ14") (class "Default")
      (node (ref "IC1") (pin "121") (pinfunction "IO_55_121") (pintype "bidirectional"))
      (node (ref "U$26") (pin "48") (pinfunction "D14_48") (pintype "bidirectional"))
    )
    (net (code "50") (name "/DQ15") (class "Default")
      (node (ref "IC1") (pin "125") (pinfunction "IO_56_125") (pintype "bidirectional"))
      (node (ref "U$26") (pin "49") (pinfunction "D15_49") (pintype "bidirectional"))
    )
    (net (code "51") (name "/FPGA_CLK") (class "Default")
      (node (ref "IC1") (pin "24") (pinfunction "CLK2_24") (pintype "bidirectional"))
      (node (ref "R27") (pin "2") (pinfunction "2_2") (pintype "passive"))
    )
    (net (code "52") (name "/GND") (class "Default")
      (node (ref "AS") (pin "10") (pinfunction "10_10") (pintype "passive"))
      (node (ref "AS") (pin "2") (pinfunction "2_2") (pintype "passive"))
      (node (ref "AUDIO_OUT") (pin "SLEEVE") (pinfunction "SLEEVE_SLEEVE") (pintype "passive"))
      (node (ref "BUTTON_0") (pin "3") (pinfunction "3_3") (pintype "bidirectional"))
      (node (ref "BUTTON_1") (pin "3") (pinfunction "3_3") (pintype "bidirectional"))
      (node (ref "BUTTON_2") (pin "3") (pinfunction "3_3") (pintype "bidirectional"))
      (node (ref "BUTTON_3") (pin "3") (pinfunction "3_3") (pintype "bidirectional"))
      (node (ref "C1") (pin "-") (pinfunction "-_-") (pintype "passive"))
      (node (ref "C10") (pin "-") (pinfunction "-_-") (pintype "passive"))
      (node (ref "C11") (pin "-") (pinfunction "-_-") (pintype "passive"))
      (node (ref "C12") (pin "2") (pinfunction "2_2") (pintype "passive"))
      (node (ref "C13") (pin "2") (pinfunction "2_2") (pintype "passive"))
      (node (ref "C14") (pin "2") (pinfunction "2_2") (pintype "passive"))
      (node (ref "C2") (pin "-") (pinfunction "-_-") (pintype "passive"))
      (node (ref "C29") (pin "2") (pinfunction "2_2") (pintype "passive"))
      (node (ref "C3") (pin "-") (pinfunction "-_-") (pintype "passive"))
      (node (ref "C30") (pin "2") (pinfunction "2_2") (pintype "passive"))
      (node (ref "C31") (pin "2") (pinfunction "2_2") (pintype "passive"))
      (node (ref "C32") (pin "2") (pinfunction "2_2") (pintype "passive"))
      (node (ref "C33") (pin "2") (pinfunction "2_2") (pintype "passive"))
      (node (ref "C34") (pin "2") (pinfunction "2_2") (pintype "passive"))
      (node (ref "C35") (pin "2") (pinfunction "2_2") (pintype "passive"))
      (node (ref "C36") (pin "2") (pinfunction "2_2") (pintype "passive"))
      (node (ref "C37") (pin "2") (pinfunction "2_2") (pintype "passive"))
      (node (ref "C38") (pin "2") (pinfunction "2_2") (pintype "passive"))
      (node (ref "C39") (pin "2") (pinfunction "2_2") (pintype "passive"))
      (node (ref "C4") (pin "2") (pinfunction "2_2") (pintype "passive"))
      (node (ref "C40") (pin "2") (pinfunction "2_2") (pintype "passive"))
      (node (ref "C41") (pin "2") (pinfunction "2_2") (pintype "passive"))
      (node (ref "C42") (pin "2") (pinfunction "2_2") (pintype "passive"))
      (node (ref "C43") (pin "2") (pinfunction "2_2") (pintype "passive"))
      (node (ref "C44") (pin "2") (pinfunction "2_2") (pintype "passive"))
      (node (ref "C45") (pin "2") (pinfunction "2_2") (pintype "passive"))
      (node (ref "C46") (pin "2") (pinfunction "2_2") (pintype "passive"))
      (node (ref "C47") (pin "2") (pinfunction "2_2") (pintype "passive"))
      (node (ref "C48") (pin "2") (pinfunction "2_2") (pintype "passive"))
      (node (ref "C49") (pin "2") (pinfunction "2_2") (pintype "passive"))
      (node (ref "C5") (pin "2") (pinfunction "2_2") (pintype "passive"))
      (node (ref "C50") (pin "2") (pinfunction "2_2") (pintype "passive"))
      (node (ref "C51") (pin "2") (pinfunction "2_2") (pintype "passive"))
      (node (ref "C52") (pin "2") (pinfunction "2_2") (pintype "passive"))
      (node (ref "C53") (pin "2") (pinfunction "2_2") (pintype "passive"))
      (node (ref "C54") (pin "2") (pinfunction "2_2") (pintype "passive"))
      (node (ref "C55") (pin "2") (pinfunction "2_2") (pintype "passive"))
      (node (ref "C56") (pin "2") (pinfunction "2_2") (pintype "passive"))
      (node (ref "C57") (pin "2") (pinfunction "2_2") (pintype "passive"))
      (node (ref "C58") (pin "2") (pinfunction "2_2") (pintype "passive"))
      (node (ref "C59") (pin "2") (pinfunction "2_2") (pintype "passive"))
      (node (ref "C6") (pin "2") (pinfunction "2_2") (pintype "passive"))
      (node (ref "C60") (pin "2") (pinfunction "2_2") (pintype "passive"))
      (node (ref "C61") (pin "2") (pinfunction "2_2") (pintype "passive"))
      (node (ref "C62") (pin "2") (pinfunction "2_2") (pintype "passive"))
      (node (ref "C7") (pin "2") (pinfunction "2_2") (pintype "passive"))
      (node (ref "C8") (pin "2") (pinfunction "2_2") (pintype "passive"))
      (node (ref "C9") (pin "2") (pinfunction "2_2") (pintype "passive"))
      (node (ref "H1") (pin "B3,0") (pinfunction "MOUNT_B3,0") (pintype "passive"))
      (node (ref "H2") (pin "B3,0") (pinfunction "MOUNT_B3,0") (pintype "passive"))
      (node (ref "H3") (pin "B3,0") (pinfunction "MOUNT_B3,0") (pintype "passive"))
      (node (ref "H4") (pin "B3,0") (pinfunction "MOUNT_B3,0") (pintype "passive"))
      (node (ref "IC1") (pin "108") (pinfunction "GNDA2_108") (pintype "bidirectional"))
      (node (ref "IC1") (pin "118") (pinfunction "GND_12_118") (pintype "bidirectional"))
      (node (ref "IC1") (pin "123") (pinfunction "GND_13_123") (pintype "bidirectional"))
      (node (ref "IC1") (pin "131") (pinfunction "GND_14_131") (pintype "bidirectional"))
      (node (ref "IC1") (pin "140") (pinfunction "GND_15_140") (pintype "bidirectional"))
      (node (ref "IC1") (pin "145") (pinfunction "EP_(GND)_145") (pintype "bidirectional"))
      (node (ref "IC1") (pin "19") (pinfunction "GND_2_19") (pintype "bidirectional"))
      (node (ref "IC1") (pin "2") (pinfunction "GNDA3_2") (pintype "bidirectional"))
      (node (ref "IC1") (pin "22") (pinfunction "GND_3_22") (pintype "bidirectional"))
      (node (ref "IC1") (pin "27") (pinfunction "GND_4_27") (pintype "bidirectional"))
      (node (ref "IC1") (pin "36") (pinfunction "GNDA1_36") (pintype "bidirectional"))
      (node (ref "IC1") (pin "4") (pinfunction "GND_1_4") (pintype "bidirectional"))
      (node (ref "IC1") (pin "41") (pinfunction "GND_5_41") (pintype "bidirectional"))
      (node (ref "IC1") (pin "48") (pinfunction "GND_6_48") (pintype "bidirectional"))
      (node (ref "IC1") (pin "57") (pinfunction "GND_7_57") (pintype "bidirectional"))
      (node (ref "IC1") (pin "63") (pinfunction "GND_8_63") (pintype "bidirectional"))
      (node (ref "IC1") (pin "74") (pinfunction "GNDA4_74") (pintype "bidirectional"))
      (node (ref "IC1") (pin "79") (pinfunction "GND_9_79") (pintype "bidirectional"))
      (node (ref "IC1") (pin "82") (pinfunction "GND_10_82") (pintype "bidirectional"))
      (node (ref "IC1") (pin "90") (pinfunction "CLK5_90") (pintype "bidirectional"))
      (node (ref "IC1") (pin "91") (pinfunction "CLK4_91") (pintype "bidirectional"))
      (node (ref "IC1") (pin "94") (pinfunction "MSEL0_94") (pintype "bidirectional"))
      (node (ref "IC1") (pin "95") (pinfunction "GND_11_95") (pintype "bidirectional"))
      (node (ref "IC1") (pin "97") (pinfunction "MSEL2_97") (pintype "bidirectional"))
      (node (ref "IC2") (pin "1") (pinfunction "DCD_1") (pintype "input"))
      (node (ref "IC2") (pin "2") (pinfunction "RI_2") (pintype "input"))
      (node (ref "IC2") (pin "23") (pinfunction "CTS_23") (pintype "input"))
      (node (ref "IC2") (pin "27") (pinfunction "DSR_27") (pintype "input"))
      (node (ref "IC2") (pin "3") (pinfunction "GND_3") (pintype "power_in"))
      (node (ref "IC2") (pin "EXP") (pinfunction "GND_EXP") (pintype "power_in"))
      (node (ref "IC2") (pin "M") (pinfunction "GND_M") (pintype "power_in"))
      (node (ref "IC3") (pin "14") (pinfunction "GND_2_14") (pintype "power_in"))
      (node (ref "IC3") (pin "19") (pinfunction "GND_3_19") (pintype "power_in"))
      (node (ref "IC3") (pin "6") (pinfunction "GND_1_6") (pintype "power_in"))
      (node (ref "J1") (pin "1") (pinfunction "1_1") (pintype "passive"))
      (node (ref "J1") (pin "2") (pinfunction "2_2") (pintype "passive"))
      (node (ref "J2") (pin "11") (pinfunction "11_11") (pintype "bidirectional"))
      (node (ref "J2") (pin "17") (pinfunction "17_17") (pintype "bidirectional"))
      (node (ref "J2") (pin "2") (pinfunction "2_2") (pintype "bidirectional"))
      (node (ref "J2") (pin "5") (pinfunction "5_5") (pintype "bidirectional"))
      (node (ref "J2") (pin "8") (pinfunction "8_8") (pintype "bidirectional"))
      (node (ref "J2") (pin "MH1") (pinfunction "MH1_MH1") (pintype "bidirectional"))
      (node (ref "J2") (pin "MH2") (pinfunction "MH2_MH2") (pintype "bidirectional"))
      (node (ref "J2") (pin "MH3") (pinfunction "MH3_MH3") (pintype "bidirectional"))
      (node (ref "J2") (pin "MH4") (pinfunction "MH4_MH4") (pintype "bidirectional"))
      (node (ref "JOYPAD1") (pin "3") (pinfunction "3_3") (pintype "passive"))
      (node (ref "JOYPAD1") (pin "S1") (pinfunction "SHIELD_S1") (pintype "bidirectional"))
      (node (ref "JOYPAD1") (pin "S2") (pinfunction "SHIELD_S2") (pintype "bidirectional"))
      (node (ref "JOYPAD1") (pin "S3") (pinfunction "SHIELD_S3") (pintype "bidirectional"))
      (node (ref "JOYPAD2") (pin "3") (pinfunction "3_3") (pintype "passive"))
      (node (ref "JOYPAD2") (pin "S1") (pinfunction "SHIELD_S1") (pintype "bidirectional"))
      (node (ref "JOYPAD2") (pin "S2") (pinfunction "SHIELD_S2") (pintype "bidirectional"))
      (node (ref "JOYPAD2") (pin "S3") (pinfunction "SHIELD_S3") (pintype "bidirectional"))
      (node (ref "JTAG") (pin "10") (pinfunction "10_10") (pintype "passive"))
      (node (ref "JTAG") (pin "2") (pinfunction "2_2") (pintype "passive"))
      (node (ref "POWER") (pin "C") (pinfunction "C_C") (pintype "passive"))
      (node (ref "PS2") (pin "3") (pinfunction "3_3") (pintype "passive"))
      (node (ref "PS2") (pin "S1") (pinfunction "SHIELD_S1") (pintype "bidirectional"))
      (node (ref "PS2") (pin "S2") (pinfunction "SHIELD_S2") (pintype "bidirectional"))
      (node (ref "PS2") (pin "S3") (pinfunction "SHIELD_S3") (pintype "bidirectional"))
      (node (ref "R14") (pin "1") (pinfunction "1_1") (pintype "passive"))
      (node (ref "R15") (pin "1") (pinfunction "1_1") (pintype "passive"))
      (node (ref "R28") (pin "1") (pinfunction "1_1") (pintype "passive"))
      (node (ref "R31") (pin "2") (pinfunction "2_2") (pintype "passive"))
      (node (ref "R41") (pin "1") (pinfunction "1_1") (pintype "passive"))
      (node (ref "R43") (pin "1") (pinfunction "1_1") (pintype "passive"))
      (node (ref "R5") (pin "1") (pinfunction "1_1") (pintype "passive"))
      (node (ref "S1") (pin "3") (pinfunction "3_3") (pintype "bidirectional"))
      (node (ref "S1") (pin "4") (pinfunction "4_4") (pintype "bidirectional"))
      (node (ref "SV1") (pin "3") (pinfunction "3_3") (pintype "passive"))
      (node (ref "SV1") (pin "4") (pinfunction "4_4") (pintype "passive"))
      (node (ref "U$1") (pin "4") (pinfunction "VSS_4") (pintype "bidirectional"))
      (node (ref "U$12") (pin "2") (pinfunction "GND_2") (pintype "bidirectional"))
      (node (ref "U$13") (pin "2") (pinfunction "E_2") (pintype "passive"))
      (node (ref "U$14") (pin "2") (pinfunction "E_2") (pintype "passive"))
      (node (ref "U$16") (pin "4") (pinfunction "VSS_4") (pintype "bidirectional"))
      (node (ref "U$18") (pin "2") (pinfunction "E_2") (pintype "passive"))
      (node (ref "U$19") (pin "2") (pinfunction "E_2") (pintype "passive"))
      (node (ref "U$20") (pin "2") (pinfunction "E_2") (pintype "passive"))
      (node (ref "U$21") (pin "2") (pinfunction "E_2") (pintype "passive"))
      (node (ref "U$26") (pin "10") (pinfunction "GNDQ_10") (pintype "power_in"))
      (node (ref "U$26") (pin "26") (pinfunction "GND_26") (pintype "power_in"))
      (node (ref "U$26") (pin "4") (pinfunction "GNDQ_4") (pintype "power_in"))
      (node (ref "U$26") (pin "41") (pinfunction "GNDQ_41") (pintype "power_in"))
      (node (ref "U$26") (pin "47") (pinfunction "GNDQ_47") (pintype "power_in"))
      (node (ref "U$26") (pin "50") (pinfunction "GND_50") (pintype "power_in"))
      (node (ref "U$5") (pin "1") (pinfunction "ADJ_1") (pintype "bidirectional"))
      (node (ref "U$6") (pin "P$1") (pinfunction "-_P$1") (pintype "passive"))
      (node (ref "U$7") (pin "1") (pinfunction "ADJ_1") (pintype "bidirectional"))
      (node (ref "U$8") (pin "1") (pinfunction "ADJ_1") (pintype "bidirectional"))
      (node (ref "U$9") (pin "1") (pinfunction "ADJ_1") (pintype "bidirectional"))
      (node (ref "X1") (pin "4") (pinfunction "4_4") (pintype "passive"))
      (node (ref "X1") (pin "S1") (pinfunction "S1_S1") (pintype "passive"))
      (node (ref "X1") (pin "S2") (pinfunction "S2_S2") (pintype "passive"))
    )
    (net (code "53") (name "/HDMI_5V") (class "Default")
      (node (ref "IC3") (pin "13") (pinfunction "5V_OUT_13") (pintype "output"))
      (node (ref "J2") (pin "18") (pinfunction "18_18") (pintype "bidirectional"))
    )
    (net (code "54") (name "/HDMI_BN") (class "Default")
      (node (ref "IC1") (pin "136") (pinfunction "IO_61_136") (pintype "bidirectional"))
      (node (ref "R7") (pin "1") (pinfunction "1_1") (pintype "passive"))
    )
    (net (code "55") (name "/HDMI_BP") (class "Default")
      (node (ref "IC1") (pin "137") (pinfunction "IO_62_137") (pintype "bidirectional"))
      (node (ref "R4") (pin "1") (pinfunction "1_1") (pintype "passive"))
    )
    (net (code "56") (name "/HDMI_CLKN") (class "Default")
      (node (ref "IC3") (pin "15") (pinfunction "CLK-_15") (pintype "input"))
      (node (ref "J2") (pin "12") (pinfunction "12_12") (pintype "bidirectional"))
      (node (ref "R19") (pin "2") (pinfunction "2_2") (pintype "passive"))
    )
    (net (code "57") (name "/HDMI_CLKP") (class "Default")
      (node (ref "IC3") (pin "16") (pinfunction "CLK+_16") (pintype "input"))
      (node (ref "J2") (pin "10") (pinfunction "10_10") (pintype "bidirectional"))
      (node (ref "R18") (pin "2") (pinfunction "2_2") (pintype "passive"))
    )
    (net (code "58") (name "/HDMI_CN") (class "Default")
      (node (ref "IC1") (pin "134") (pinfunction "IO_59_134") (pintype "bidirectional"))
      (node (ref "R19") (pin "1") (pinfunction "1_1") (pintype "passive"))
    )
    (net (code "59") (name "/HDMI_CP") (class "Default")
      (node (ref "IC1") (pin "135") (pinfunction "IO_60_135") (pintype "bidirectional"))
      (node (ref "R18") (pin "1") (pinfunction "1_1") (pintype "passive"))
    )
    (net (code "60") (name "/HDMI_D0N") (class "Default")
      (node (ref "IC3") (pin "17") (pinfunction "D0-_17") (pintype "bidirectional"))
      (node (ref "J2") (pin "9") (pinfunction "9_9") (pintype "bidirectional"))
      (node (ref "R7") (pin "2") (pinfunction "2_2") (pintype "passive"))
    )
    (net (code "61") (name "/HDMI_D0P") (class "Default")
      (node (ref "IC3") (pin "18") (pinfunction "D0+_18") (pintype "bidirectional"))
      (node (ref "J2") (pin "7") (pinfunction "7_7") (pintype "bidirectional"))
      (node (ref "R4") (pin "2") (pinfunction "2_2") (pintype "passive"))
    )
    (net (code "62") (name "/HDMI_D1N") (class "Default")
      (node (ref "IC3") (pin "20") (pinfunction "D1-_20") (pintype "bidirectional"))
      (node (ref "J2") (pin "6") (pinfunction "6_6") (pintype "bidirectional"))
      (node (ref "R9") (pin "2") (pinfunction "2_2") (pintype "passive"))
    )
    (net (code "63") (name "/HDMI_D1P") (class "Default")
      (node (ref "IC3") (pin "21") (pinfunction "D1+_21") (pintype "bidirectional"))
      (node (ref "J2") (pin "4") (pinfunction "4_4") (pintype "bidirectional"))
      (node (ref "R8") (pin "2") (pinfunction "2_2") (pintype "passive"))
    )
    (net (code "64") (name "/HDMI_D2N") (class "Default")
      (node (ref "IC3") (pin "22") (pinfunction "D2-_22") (pintype "bidirectional"))
      (node (ref "J2") (pin "3") (pinfunction "3_3") (pintype "bidirectional"))
      (node (ref "R17") (pin "2") (pinfunction "2_2") (pintype "passive"))
    )
    (net (code "65") (name "/HDMI_D2P") (class "Default")
      (node (ref "IC3") (pin "23") (pinfunction "D2+_23") (pintype "bidirectional"))
      (node (ref "J2") (pin "1") (pinfunction "1_1") (pintype "bidirectional"))
      (node (ref "R16") (pin "2") (pinfunction "2_2") (pintype "passive"))
    )
    (net (code "66") (name "/HDMI_GN") (class "Default")
      (node (ref "IC1") (pin "141") (pinfunction "IO_63_141") (pintype "bidirectional"))
      (node (ref "R9") (pin "1") (pinfunction "1_1") (pintype "passive"))
    )
    (net (code "67") (name "/HDMI_GP") (class "Default")
      (node (ref "IC1") (pin "142") (pinfunction "IO_64_142") (pintype "bidirectional"))
      (node (ref "R8") (pin "1") (pinfunction "1_1") (pintype "passive"))
    )
    (net (code "68") (name "/HDMI_RN") (class "Default")
      (node (ref "IC1") (pin "143") (pinfunction "IO_65_143") (pintype "bidirectional"))
      (node (ref "R17") (pin "1") (pinfunction "1_1") (pintype "passive"))
    )
    (net (code "69") (name "/HDMI_RP") (class "Default")
      (node (ref "IC1") (pin "144") (pinfunction "IO_66_144") (pintype "bidirectional"))
      (node (ref "R16") (pin "1") (pinfunction "1_1") (pintype "passive"))
    )
    (net (code "70") (name "/HPD_B") (class "Default")
      (node (ref "IC3") (pin "10") (pinfunction "HPD_B-_10") (pintype "bidirectional"))
      (node (ref "J2") (pin "19") (pinfunction "19_19") (pintype "bidirectional"))
    )
    (net (code "71") (name "/JP1_CLK") (class "Default")
      (node (ref "JOYPAD1") (pin "5") (pinfunction "5_5") (pintype "passive"))
      (node (ref "R35") (pin "2") (pinfunction "2_2") (pintype "passive"))
      (node (ref "U$18") (pin "3") (pinfunction "C_3") (pintype "passive"))
    )
    (net (code "72") (name "/JP1_CLK_Q") (class "Default")
      (node (ref "IC1") (pin "49") (pinfunction "IO_17_49") (pintype "bidirectional"))
      (node (ref "R39") (pin "1") (pinfunction "1_1") (pintype "passive"))
    )
    (net (code "73") (name "/JP1_DATA") (class "Default")
      (node (ref "JOYPAD1") (pin "1") (pinfunction "1_1") (pintype "passive"))
      (node (ref "R40") (pin "2") (pinfunction "2_2") (pintype "passive"))
    )
    (net (code "74") (name "/JP1_DATA_D") (class "Default")
      (node (ref "IC1") (pin "88") (pinfunction "CLK7_88") (pintype "bidirectional"))
      (node (ref "R40") (pin "1") (pinfunction "1_1") (pintype "passive"))
      (node (ref "R41") (pin "2") (pinfunction "2_2") (pintype "passive"))
    )
    (net (code "75") (name "/JP1_LATCH") (class "Default")
      (node (ref "JOYPAD1") (pin "6") (pinfunction "6_6") (pintype "passive"))
      (node (ref "R34") (pin "2") (pinfunction "2_2") (pintype "passive"))
      (node (ref "U$19") (pin "3") (pinfunction "C_3") (pintype "passive"))
    )
    (net (code "76") (name "/JP1_LATCH_Q") (class "Default")
      (node (ref "IC1") (pin "46") (pinfunction "IO_16_46") (pintype "bidirectional"))
      (node (ref "R38") (pin "1") (pinfunction "1_1") (pintype "passive"))
    )
    (net (code "77") (name "/JP2_CLK") (class "Default")
      (node (ref "JOYPAD2") (pin "5") (pinfunction "5_5") (pintype "passive"))
      (node (ref "R33") (pin "2") (pinfunction "2_2") (pintype "passive"))
      (node (ref "U$20") (pin "3") (pinfunction "C_3") (pintype "passive"))
    )
    (net (code "78") (name "/JP2_CLK_Q") (class "Default")
      (node (ref "IC1") (pin "51") (pinfunction "IO_19_51") (pintype "bidirectional"))
      (node (ref "R37") (pin "1") (pinfunction "1_1") (pintype "passive"))
    )
    (net (code "79") (name "/JP2_DATA") (class "Default")
      (node (ref "JOYPAD2") (pin "1") (pinfunction "1_1") (pintype "passive"))
      (node (ref "R42") (pin "2") (pinfunction "2_2") (pintype "passive"))
    )
    (net (code "80") (name "/JP2_DATA_D") (class "Default")
      (node (ref "IC1") (pin "89") (pinfunction "CLK6_89") (pintype "bidirectional"))
      (node (ref "R42") (pin "1") (pinfunction "1_1") (pintype "passive"))
      (node (ref "R43") (pin "2") (pinfunction "2_2") (pintype "passive"))
    )
    (net (code "81") (name "/JP2_LATCH") (class "Default")
      (node (ref "JOYPAD2") (pin "6") (pinfunction "6_6") (pintype "passive"))
      (node (ref "R32") (pin "2") (pinfunction "2_2") (pintype "passive"))
      (node (ref "U$21") (pin "3") (pinfunction "C_3") (pintype "passive"))
    )
    (net (code "82") (name "/JP2_LATCH_Q") (class "Default")
      (node (ref "IC1") (pin "50") (pinfunction "IO_18_50") (pintype "bidirectional"))
      (node (ref "R36") (pin "1") (pinfunction "1_1") (pintype "passive"))
    )
    (net (code "83") (name "/LDQM") (class "Default")
      (node (ref "IC1") (pin "98") (pinfunction "IO_39_98") (pintype "bidirectional"))
      (node (ref "U$26") (pin "14") (pinfunction "LDQM_14") (pintype "input"))
    )
    (net (code "84") (name "/PMOD_0") (class "Default")
      (node (ref "IC1") (pin "44") (pinfunction "IO_15_44") (pintype "bidirectional"))
      (node (ref "SV1") (pin "11") (pinfunction "11_11") (pintype "passive"))
    )
    (net (code "85") (name "/PMOD_1") (class "Default")
      (node (ref "IC1") (pin "42") (pinfunction "IO_13_42") (pintype "bidirectional"))
      (node (ref "SV1") (pin "9") (pinfunction "9_9") (pintype "passive"))
    )
    (net (code "86") (name "/PMOD_2") (class "Default")
      (node (ref "IC1") (pin "33") (pinfunction "IO_11_33") (pintype "bidirectional"))
      (node (ref "SV1") (pin "7") (pinfunction "7_7") (pintype "passive"))
    )
    (net (code "87") (name "/PMOD_3") (class "Default")
      (node (ref "IC1") (pin "31") (pinfunction "IO_9_31") (pintype "bidirectional"))
      (node (ref "SV1") (pin "5") (pinfunction "5_5") (pintype "passive"))
    )
    (net (code "88") (name "/PMOD_4") (class "Default")
      (node (ref "IC1") (pin "43") (pinfunction "IO_14_43") (pintype "bidirectional"))
      (node (ref "SV1") (pin "12") (pinfunction "12_12") (pintype "passive"))
    )
    (net (code "89") (name "/PMOD_5") (class "Default")
      (node (ref "IC1") (pin "39") (pinfunction "IO_12_39") (pintype "bidirectional"))
      (node (ref "SV1") (pin "10") (pinfunction "10_10") (pintype "passive"))
    )
    (net (code "90") (name "/PMOD_6") (class "Default")
      (node (ref "IC1") (pin "32") (pinfunction "IO_10_32") (pintype "bidirectional"))
      (node (ref "SV1") (pin "8") (pinfunction "8_8") (pintype "passive"))
    )
    (net (code "91") (name "/PMOD_7") (class "Default")
      (node (ref "IC1") (pin "30") (pinfunction "IO_8_30") (pintype "bidirectional"))
      (node (ref "SV1") (pin "6") (pinfunction "6_6") (pintype "passive"))
    )
    (net (code "92") (name "/PS2_CLK") (class "Default")
      (node (ref "PS2") (pin "5") (pinfunction "5_5") (pintype "passive"))
      (node (ref "R11") (pin "2") (pinfunction "2_2") (pintype "passive"))
      (node (ref "R13") (pin "2") (pinfunction "2_2") (pintype "passive"))
      (node (ref "U$14") (pin "3") (pinfunction "C_3") (pintype "passive"))
    )
    (net (code "93") (name "/PS2_CLK_D") (class "Default")
      (node (ref "IC1") (pin "127") (pinfunction "CLK9_127") (pintype "bidirectional"))
      (node (ref "R13") (pin "1") (pinfunction "1_1") (pintype "passive"))
      (node (ref "R15") (pin "2") (pinfunction "2_2") (pintype "passive"))
    )
    (net (code "94") (name "/PS2_CLK_Q") (class "Default")
      (node (ref "IC1") (pin "133") (pinfunction "IO_58_133") (pintype "bidirectional"))
      (node (ref "R3") (pin "1") (pinfunction "1_1") (pintype "passive"))
    )
    (net (code "95") (name "/PS2_DATA") (class "Default")
      (node (ref "PS2") (pin "1") (pinfunction "1_1") (pintype "passive"))
      (node (ref "R10") (pin "2") (pinfunction "2_2") (pintype "passive"))
      (node (ref "R12") (pin "2") (pinfunction "2_2") (pintype "passive"))
      (node (ref "U$13") (pin "3") (pinfunction "C_3") (pintype "passive"))
    )
    (net (code "96") (name "/PS2_DATA_D") (class "Default")
      (node (ref "IC1") (pin "126") (pinfunction "CLK8_126") (pintype "bidirectional"))
      (node (ref "R12") (pin "1") (pinfunction "1_1") (pintype "passive"))
      (node (ref "R14") (pin "2") (pinfunction "2_2") (pintype "passive"))
    )
    (net (code "97") (name "/PS2_DATA_Q") (class "Default")
      (node (ref "IC1") (pin "132") (pinfunction "IO_57_132") (pintype "bidirectional"))
      (node (ref "R2") (pin "1") (pinfunction "1_1") (pintype "passive"))
    )
    (net (code "98") (name "/RESET") (class "Default")
      (node (ref "C57") (pin "1") (pinfunction "1_1") (pintype "passive"))
      (node (ref "IC1") (pin "25") (pinfunction "CLK3_25") (pintype "bidirectional"))
      (node (ref "R44") (pin "1") (pinfunction "1_1") (pintype "passive"))
      (node (ref "S1") (pin "2") (pinfunction "2_2") (pintype "bidirectional"))
    )
    (net (code "99") (name "/RW") (class "Default")
      (node (ref "IC1") (pin "87") (pinfunction "IO_38_87") (pintype "bidirectional"))
      (node (ref "U$26") (pin "15") (pinfunction "~{WE}_15") (pintype "input"))
    )
    (net (code "100") (name "/SCL_B") (class "Default")
      (node (ref "IC3") (pin "8") (pinfunction "SCL_B_8") (pintype "bidirectional"))
      (node (ref "J2") (pin "15") (pinfunction "15_15") (pintype "bidirectional"))
    )
    (net (code "101") (name "/SDA_B") (class "Default")
      (node (ref "IC3") (pin "9") (pinfunction "SDA_B_9") (pintype "bidirectional"))
      (node (ref "J2") (pin "16") (pinfunction "16_16") (pintype "bidirectional"))
    )
    (net (code "102") (name "/SDRAM_CLK") (class "Default")
      (node (ref "IC1") (pin "71") (pinfunction "IO_30_71") (pintype "bidirectional"))
      (node (ref "U$26") (pin "35") (pinfunction "CLK_35") (pintype "input"))
    )
    (net (code "103") (name "/TCK") (class "Default")
      (node (ref "IC1") (pin "16") (pinfunction "TCK_16") (pintype "bidirectional"))
      (node (ref "JTAG") (pin "1") (pinfunction "1_1") (pintype "passive"))
      (node (ref "R28") (pin "2") (pinfunction "2_2") (pintype "passive"))
    )
    (net (code "104") (name "/TDI") (class "Default")
      (node (ref "IC1") (pin "15") (pinfunction "TDI_15") (pintype "bidirectional"))
      (node (ref "JTAG") (pin "9") (pinfunction "9_9") (pintype "passive"))
      (node (ref "R30") (pin "2") (pinfunction "2_2") (pintype "passive"))
    )
    (net (code "105") (name "/TDO") (class "Default")
      (node (ref "IC1") (pin "20") (pinfunction "TDO_20") (pintype "bidirectional"))
      (node (ref "JTAG") (pin "3") (pinfunction "3_3") (pintype "passive"))
    )
    (net (code "106") (name "/TMS") (class "Default")
      (node (ref "IC1") (pin "18") (pinfunction "TMS_18") (pintype "bidirectional"))
      (node (ref "JTAG") (pin "5") (pinfunction "5_5") (pintype "passive"))
      (node (ref "R29") (pin "2") (pinfunction "2_2") (pintype "passive"))
    )
    (net (code "107") (name "/UDQM") (class "Default")
      (node (ref "IC1") (pin "111") (pinfunction "IO_48_111") (pintype "bidirectional"))
      (node (ref "U$26") (pin "36") (pinfunction "UDQM_36") (pintype "input"))
    )
    (net (code "108") (name "/~{CAS}") (class "Default")
      (node (ref "IC1") (pin "86") (pinfunction "IO_37_86") (pintype "bidirectional"))
      (node (ref "U$26") (pin "16") (pinfunction "~{CAS}_16") (pintype "input"))
    )
    (net (code "109") (name "/~{CE}") (class "Default")
      (node (ref "AS") (pin "6") (pinfunction "6_6") (pintype "passive"))
      (node (ref "IC1") (pin "21") (pinfunction "NCE_21") (pintype "bidirectional"))
      (node (ref "R31") (pin "1") (pinfunction "1_1") (pintype "passive"))
    )
    (net (code "110") (name "/~{CONFIG}") (class "Default")
      (node (ref "AS") (pin "5") (pinfunction "5_5") (pintype "passive"))
      (node (ref "IC1") (pin "14") (pinfunction "NCONFIG_14") (pintype "bidirectional"))
      (node (ref "R58") (pin "2") (pinfunction "2_2") (pintype "passive"))
    )
    (net (code "111") (name "/~{CSO}") (class "Default")
      (node (ref "AS") (pin "8") (pinfunction "8_8") (pintype "passive"))
      (node (ref "IC1") (pin "8") (pinfunction "IO_3_8") (pintype "bidirectional"))
      (node (ref "U$16") (pin "1") (pinfunction "~{CS}_1") (pintype "bidirectional"))
    )
    (net (code "112") (name "/~{CS}") (class "Default")
      (node (ref "IC1") (pin "59") (pinfunction "IO_21_59") (pintype "bidirectional"))
      (node (ref "U$26") (pin "18") (pinfunction "~{CS}_18") (pintype "input"))
    )
    (net (code "113") (name "/~{RAS}") (class "Default")
      (node (ref "IC1") (pin "85") (pinfunction "IO_36_85") (pintype "bidirectional"))
      (node (ref "U$26") (pin "17") (pinfunction "~{RAS}_17") (pintype "input"))
    )
    (net (code "114") (name "Net-(AUDIO_OUT-PadRING)") (class "Default")
      (node (ref "AUDIO_OUT") (pin "RING") (pinfunction "RING_RING") (pintype "passive"))
      (node (ref "AUDIO_OUT") (pin "TIP") (pinfunction "TIP_TIP") (pintype "passive"))
      (node (ref "C21") (pin "1") (pinfunction "1_1") (pintype "passive"))
      (node (ref "R5") (pin "2") (pinfunction "2_2") (pintype "passive"))
    )
    (net (code "115") (name "Net-(C21-Pad2)") (class "Default")
      (node (ref "C21") (pin "2") (pinfunction "2_2") (pintype "passive"))
      (node (ref "R6") (pin "2") (pinfunction "2_2") (pintype "passive"))
    )
    (net (code "116") (name "Net-(D1-PadA)") (class "Default")
      (node (ref "D1") (pin "A") (pinfunction "A_A") (pintype "passive"))
      (node (ref "J1") (pin "3") (pinfunction "3_3") (pintype "passive"))
    )
    (net (code "117") (name "Net-(IC1-NSTATUS)") (class "Default")
      (node (ref "IC1") (pin "9") (pinfunction "NSTATUS_9") (pintype "bidirectional"))
      (node (ref "R57") (pin "2") (pinfunction "2_2") (pintype "passive"))
    )
    (net (code "118") (name "Net-(IC1-VCCD_PLL1)") (class "Default")
      (node (ref "C60") (pin "1") (pinfunction "1_1") (pintype "passive"))
      (node (ref "IC1") (pin "37") (pinfunction "VCCD_PLL1_37") (pintype "bidirectional"))
      (node (ref "U$23") (pin "2") (pinfunction "2_2") (pintype "passive"))
    )
    (net (code "119") (name "Net-(IC1-VCCD_PLL2)") (class "Default")
      (node (ref "C62") (pin "1") (pinfunction "1_1") (pintype "passive"))
      (node (ref "IC1") (pin "109") (pinfunction "VCCD_PLL2_109") (pintype "bidirectional"))
      (node (ref "U$25") (pin "1") (pinfunction "1_1") (pintype "passive"))
    )
    (net (code "120") (name "Net-(IC1-VCCD_PLL3)") (class "Default")
      (node (ref "C59") (pin "1") (pinfunction "1_1") (pintype "passive"))
      (node (ref "IC1") (pin "1") (pinfunction "VCCD_PLL3_1") (pintype "bidirectional"))
      (node (ref "U$22") (pin "2") (pinfunction "2_2") (pintype "passive"))
    )
    (net (code "121") (name "Net-(IC1-VCCD_PLL4)") (class "Default")
      (node (ref "C61") (pin "1") (pinfunction "1_1") (pintype "passive"))
      (node (ref "IC1") (pin "73") (pinfunction "VCCD_PLL4_73") (pintype "bidirectional"))
      (node (ref "U$24") (pin "1") (pinfunction "1_1") (pintype "passive"))
    )
    (net (code "122") (name "Net-(IC2-D+)") (class "Default")
      (node (ref "IC2") (pin "4") (pinfunction "D+_4") (pintype "bidirectional"))
      (node (ref "X1") (pin "3") (pinfunction "3_3") (pintype "passive"))
    )
    (net (code "123") (name "Net-(IC2-D-)") (class "Default")
      (node (ref "IC2") (pin "5") (pinfunction "D-_5") (pintype "bidirectional"))
      (node (ref "X1") (pin "2") (pinfunction "2_2") (pintype "passive"))
    )
    (net (code "124") (name "Net-(IC2-REGIN)") (class "Default")
      (node (ref "C13") (pin "1") (pinfunction "1_1") (pintype "passive"))
      (node (ref "D2") (pin "A") (pinfunction "A_A") (pintype "passive"))
      (node (ref "IC2") (pin "7") (pinfunction "REGIN_7") (pintype "passive"))
      (node (ref "IC2") (pin "8") (pinfunction "VBUS_8") (pintype "input"))
      (node (ref "X1") (pin "1") (pinfunction "1_1") (pintype "passive"))
    )
    (net (code "125") (name "Net-(IC2-VDD)") (class "Default")
      (node (ref "C12") (pin "1") (pinfunction "1_1") (pintype "passive"))
      (node (ref "C14") (pin "1") (pinfunction "1_1") (pintype "passive"))
      (node (ref "IC2") (pin "6") (pinfunction "VDD_6") (pintype "power_in"))
      (node (ref "R1") (pin "1") (pinfunction "1_1") (pintype "passive"))
    )
    (net (code "126") (name "Net-(IC2-~{RST})") (class "Default")
      (node (ref "IC2") (pin "9") (pinfunction "~{RST}_9") (pintype "bidirectional"))
      (node (ref "R1") (pin "2") (pinfunction "2_2") (pintype "passive"))
    )
    (net (code "127") (name "Net-(POWER-PadA)") (class "Default")
      (node (ref "POWER") (pin "A") (pinfunction "A_A") (pintype "passive"))
      (node (ref "R56") (pin "2") (pinfunction "2_2") (pintype "passive"))
    )
    (net (code "128") (name "Net-(U$5-IN)") (class "Default")
      (node (ref "C4") (pin "1") (pinfunction "1_1") (pintype "passive"))
      (node (ref "D1") (pin "C") (pinfunction "C_C") (pintype "passive"))
      (node (ref "U$5") (pin "3") (pinfunction "IN_3") (pintype "bidirectional"))
      (node (ref "U$6") (pin "P$2") (pinfunction "+_P$2") (pintype "passive"))
    )
    (net (code "129") (name "Net-(U$12-OUT)") (class "Default")
      (node (ref "R27") (pin "1") (pinfunction "1_1") (pintype "passive"))
      (node (ref "U$12") (pin "3") (pinfunction "OUT_3") (pintype "bidirectional"))
    )
    (net (code "130") (name "Net-(U$13-B)") (class "Default")
      (node (ref "R2") (pin "2") (pinfunction "2_2") (pintype "passive"))
      (node (ref "U$13") (pin "1") (pinfunction "B_1") (pintype "passive"))
    )
    (net (code "131") (name "Net-(U$14-B)") (class "Default")
      (node (ref "R3") (pin "2") (pinfunction "2_2") (pintype "passive"))
      (node (ref "U$14") (pin "1") (pinfunction "B_1") (pintype "passive"))
    )
    (net (code "132") (name "Net-(U$16-SO)") (class "Default")
      (node (ref "R26") (pin "2") (pinfunction "2_2") (pintype "passive"))
      (node (ref "U$16") (pin "2") (pinfunction "SO_2") (pintype "bidirectional"))
    )
    (net (code "133") (name "Net-(U$18-B)") (class "Default")
      (node (ref "R39") (pin "2") (pinfunction "2_2") (pintype "passive"))
      (node (ref "U$18") (pin "1") (pinfunction "B_1") (pintype "passive"))
    )
    (net (code "134") (name "Net-(U$19-B)") (class "Default")
      (node (ref "R38") (pin "2") (pinfunction "2_2") (pintype "passive"))
      (node (ref "U$19") (pin "1") (pinfunction "B_1") (pintype "passive"))
    )
    (net (code "135") (name "Net-(U$20-B)") (class "Default")
      (node (ref "R37") (pin "2") (pinfunction "2_2") (pintype "passive"))
      (node (ref "U$20") (pin "1") (pinfunction "B_1") (pintype "passive"))
    )
    (net (code "136") (name "Net-(U$21-B)") (class "Default")
      (node (ref "R36") (pin "2") (pinfunction "2_2") (pintype "passive"))
      (node (ref "U$21") (pin "1") (pinfunction "B_1") (pintype "passive"))
    )
    (net (code "137") (name "unconnected-(AUDIO_OUT-PadRING_SWITCH)") (class "Default")
      (node (ref "AUDIO_OUT") (pin "RING_SWITCH") (pinfunction "RING_SWITCH_RING_SWITCH") (pintype "passive"))
    )
    (net (code "138") (name "unconnected-(AUDIO_OUT-PadTIP_SWITCH)") (class "Default")
      (node (ref "AUDIO_OUT") (pin "TIP_SWITCH") (pinfunction "TIP_SWITCH_TIP_SWITCH") (pintype "passive"))
    )
    (net (code "139") (name "unconnected-(BUTTON_0-Pad1)") (class "Default")
      (node (ref "BUTTON_0") (pin "1") (pinfunction "1_1") (pintype "bidirectional"))
    )
    (net (code "140") (name "unconnected-(BUTTON_0-Pad4)") (class "Default")
      (node (ref "BUTTON_0") (pin "4") (pinfunction "4_4") (pintype "bidirectional"))
    )
    (net (code "141") (name "unconnected-(BUTTON_1-Pad1)") (class "Default")
      (node (ref "BUTTON_1") (pin "1") (pinfunction "1_1") (pintype "bidirectional"))
    )
    (net (code "142") (name "unconnected-(BUTTON_1-Pad4)") (class "Default")
      (node (ref "BUTTON_1") (pin "4") (pinfunction "4_4") (pintype "bidirectional"))
    )
    (net (code "143") (name "unconnected-(BUTTON_2-Pad1)") (class "Default")
      (node (ref "BUTTON_2") (pin "1") (pinfunction "1_1") (pintype "bidirectional"))
    )
    (net (code "144") (name "unconnected-(BUTTON_2-Pad4)") (class "Default")
      (node (ref "BUTTON_2") (pin "4") (pinfunction "4_4") (pintype "bidirectional"))
    )
    (net (code "145") (name "unconnected-(BUTTON_3-Pad1)") (class "Default")
      (node (ref "BUTTON_3") (pin "1") (pinfunction "1_1") (pintype "bidirectional"))
    )
    (net (code "146") (name "unconnected-(BUTTON_3-Pad4)") (class "Default")
      (node (ref "BUTTON_3") (pin "4") (pinfunction "4_4") (pintype "bidirectional"))
    )
    (net (code "147") (name "unconnected-(IC2-DTR-Pad28)") (class "Default")
      (node (ref "IC2") (pin "28") (pinfunction "DTR_28") (pintype "output"))
    )
    (net (code "148") (name "unconnected-(IC2-SUSPEND-Pad12)") (class "Default")
      (node (ref "IC2") (pin "12") (pinfunction "SUSPEND_12") (pintype "output"))
    )
    (net (code "149") (name "unconnected-(IC2-~{SUSPEND}-Pad11)") (class "Default")
      (node (ref "IC2") (pin "11") (pinfunction "~{SUSPEND}_11") (pintype "output"))
    )
    (net (code "150") (name "unconnected-(IC3-CEC_A-Pad1)") (class "Default")
      (node (ref "IC3") (pin "1") (pinfunction "CEC_A_1") (pintype "bidirectional"))
    )
    (net (code "151") (name "unconnected-(IC3-HPD_A--Pad4)") (class "Default")
      (node (ref "IC3") (pin "4") (pinfunction "HPD_A-_4") (pintype "bidirectional"))
    )
    (net (code "152") (name "unconnected-(IC3-SCL_A-Pad2)") (class "Default")
      (node (ref "IC3") (pin "2") (pinfunction "SCL_A_2") (pintype "bidirectional"))
    )
    (net (code "153") (name "unconnected-(IC3-SDA_A-Pad3)") (class "Default")
      (node (ref "IC3") (pin "3") (pinfunction "SDA_A_3") (pintype "bidirectional"))
    )
    (net (code "154") (name "unconnected-(J2-Pad14)") (class "Default")
      (node (ref "J2") (pin "14") (pinfunction "14_14") (pintype "bidirectional"))
    )
    (net (code "155") (name "unconnected-(JOYPAD1-Pad2)") (class "Default")
      (node (ref "JOYPAD1") (pin "2") (pinfunction "2_2") (pintype "passive"))
    )
    (net (code "156") (name "unconnected-(JOYPAD2-Pad2)") (class "Default")
      (node (ref "JOYPAD2") (pin "2") (pinfunction "2_2") (pintype "passive"))
    )
    (net (code "157") (name "unconnected-(JTAG-Pad6)") (class "Default")
      (node (ref "JTAG") (pin "6") (pinfunction "6_6") (pintype "passive"))
    )
    (net (code "158") (name "unconnected-(JTAG-Pad7)") (class "Default")
      (node (ref "JTAG") (pin "7") (pinfunction "7_7") (pintype "passive"))
    )
    (net (code "159") (name "unconnected-(JTAG-Pad8)") (class "Default")
      (node (ref "JTAG") (pin "8") (pinfunction "8_8") (pintype "passive"))
    )
    (net (code "160") (name "unconnected-(PS2-Pad2)") (class "Default")
      (node (ref "PS2") (pin "2") (pinfunction "2_2") (pintype "passive"))
    )
    (net (code "161") (name "unconnected-(PS2-Pad6)") (class "Default")
      (node (ref "PS2") (pin "6") (pinfunction "6_6") (pintype "passive"))
    )
    (net (code "162") (name "unconnected-(S1-Pad1)") (class "Default")
      (node (ref "S1") (pin "1") (pinfunction "1_1") (pintype "bidirectional"))
    )
    (net (code "163") (name "unconnected-(U$1-~{HOLD}-Pad7)") (class "Default")
      (node (ref "U$1") (pin "7") (pinfunction "~{HOLD}_7") (pintype "bidirectional"))
    )
  )
)
